# ECDL_CUR_CTRL.net
KiCad netlist of a schematic drawn in EAGLE
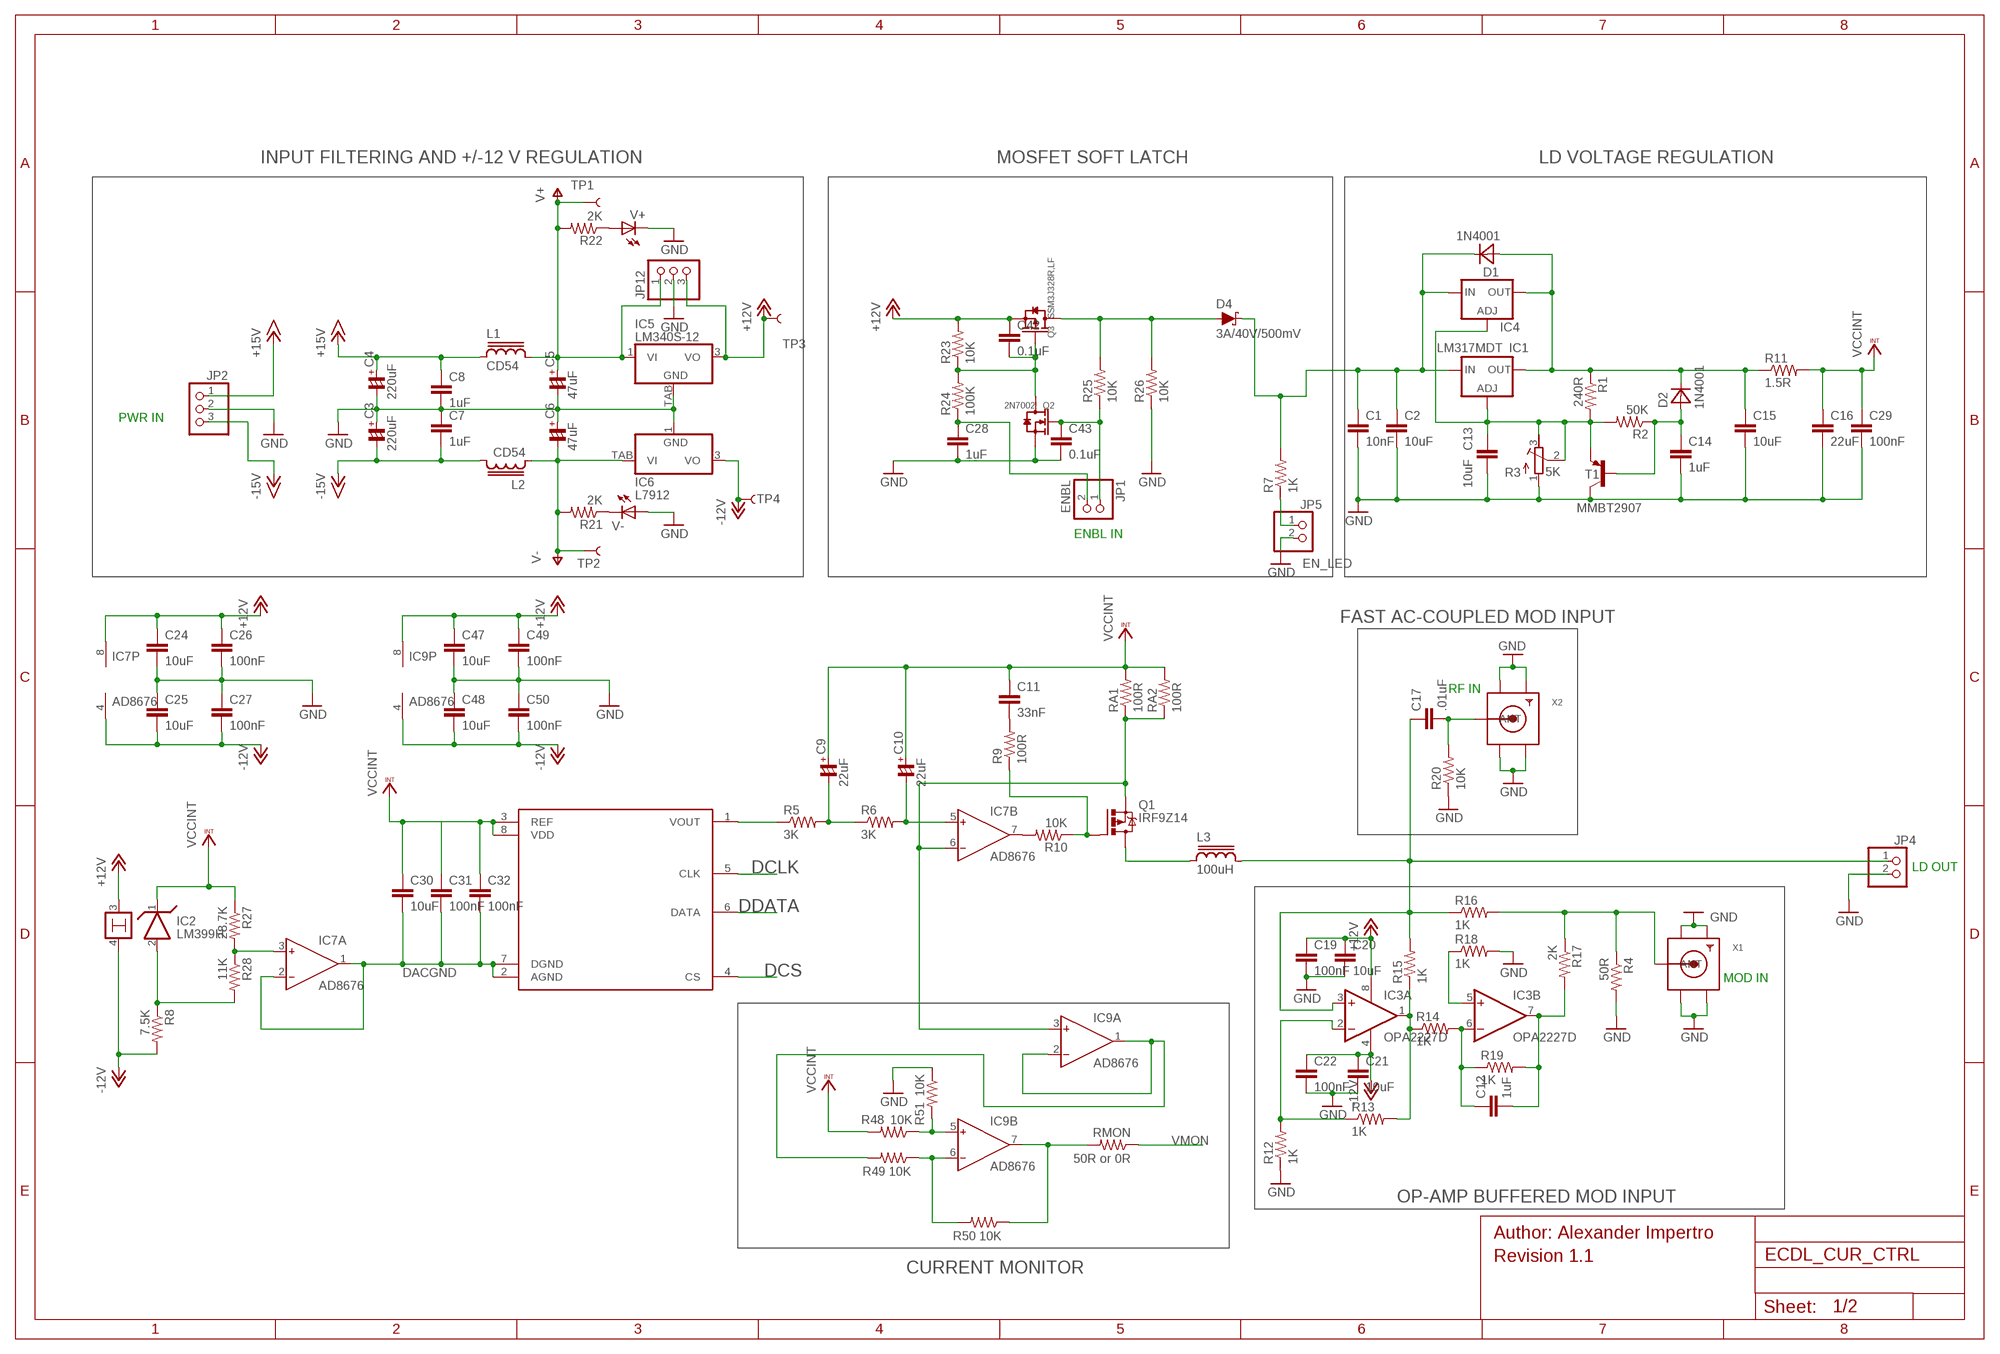
[diagram p0: schematic, sheet 1]
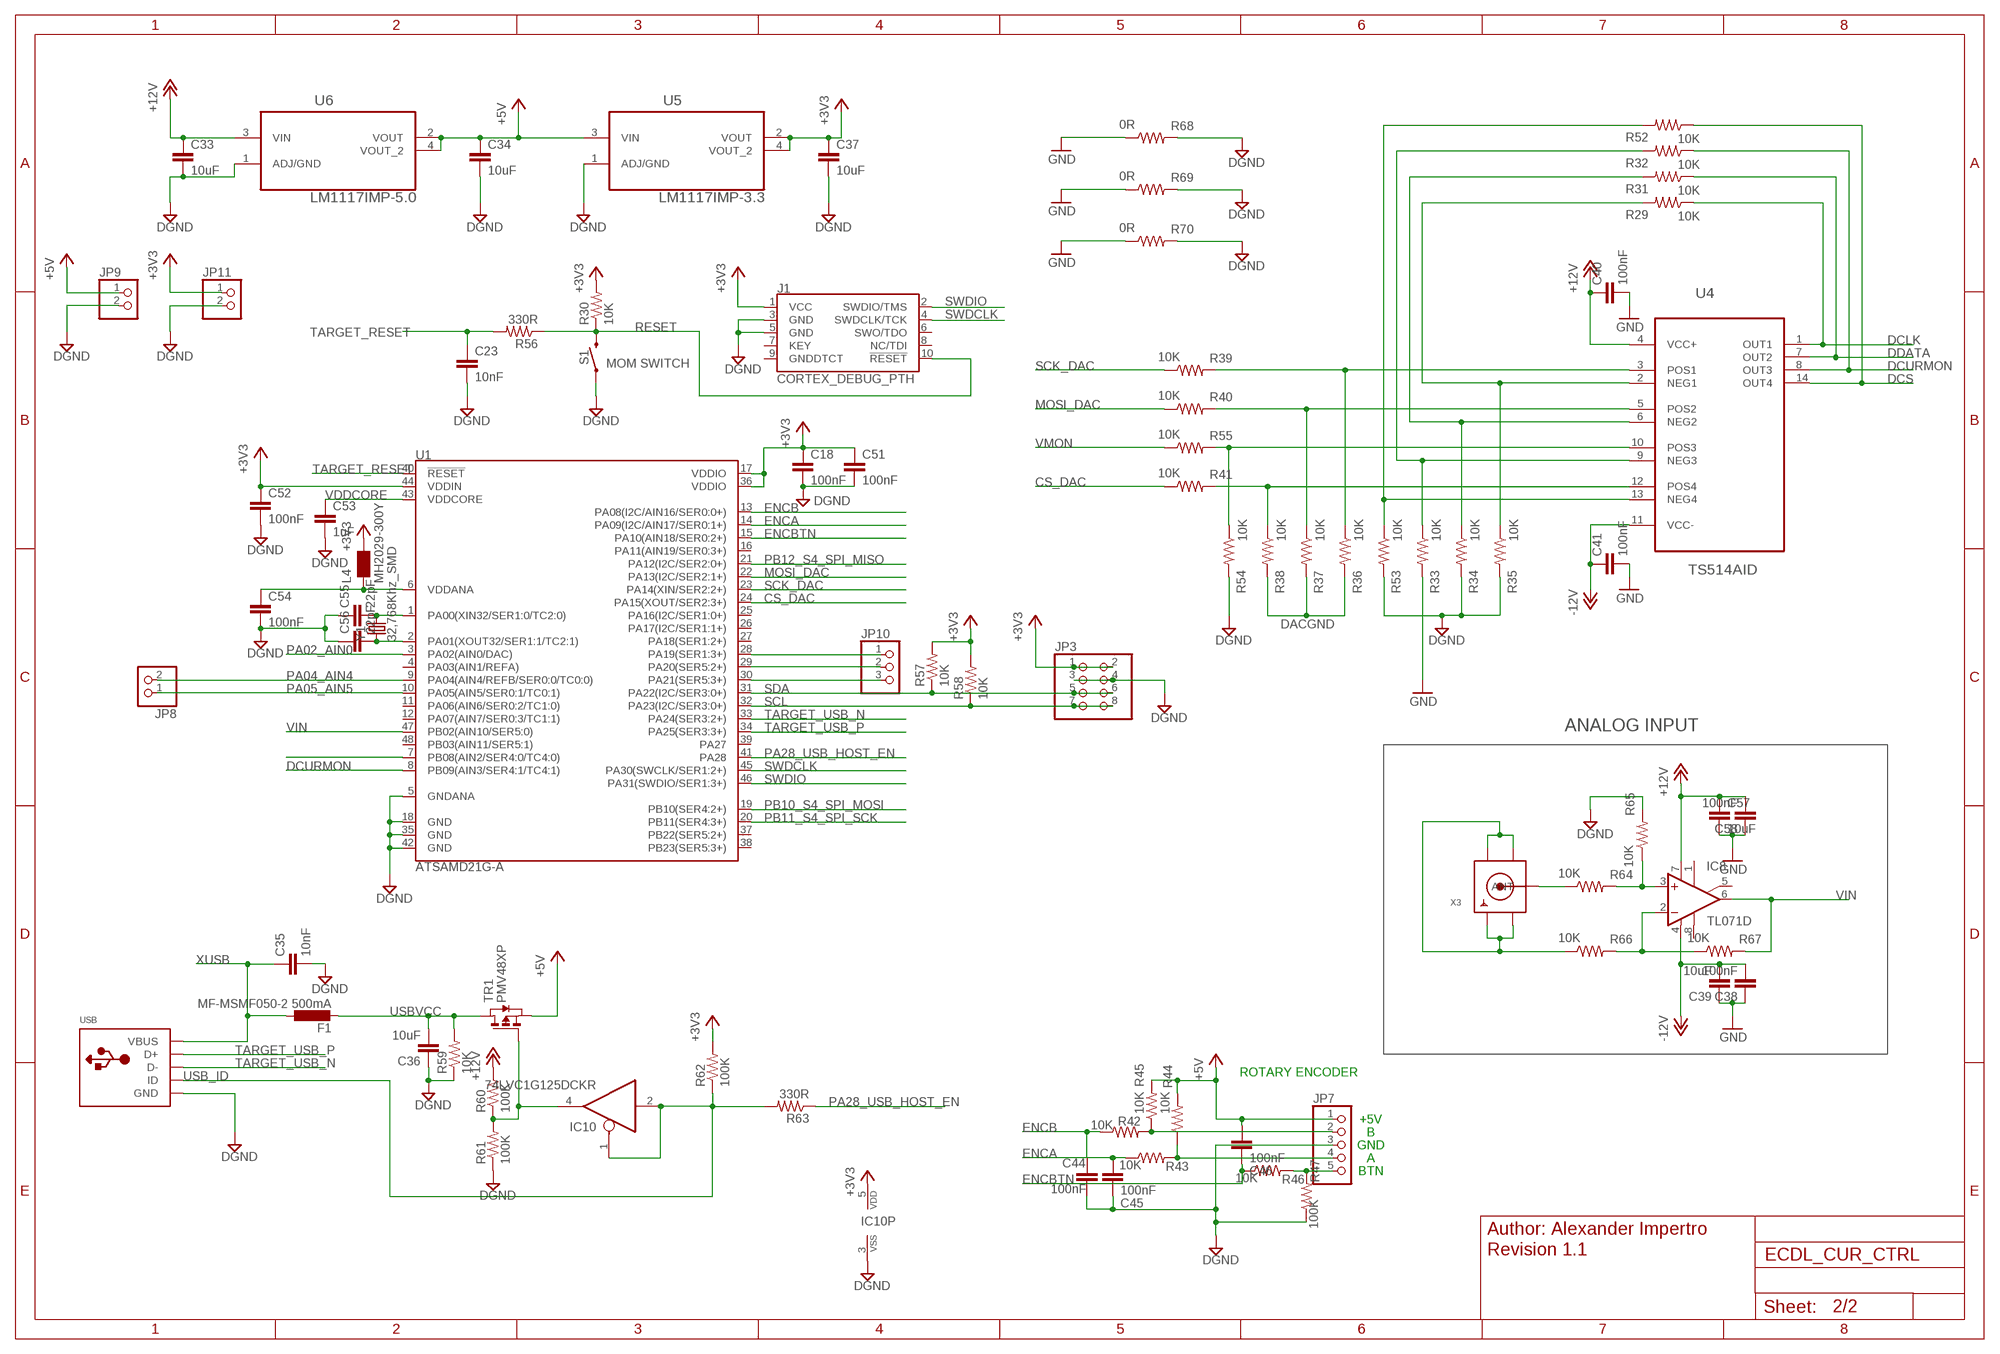
[diagram p1: schematic, sheet 2]

(export (version "E")
  (design (tool "Eeschema 10.0.6"))
  (components
    (comp (ref "C1")
      (value "10nF")
      (footprint "eagle-import:C0805")
      (libsource (lib "eagle-import") (part "C-EUC0805"))
    )
    (comp (ref "C2")
      (value "10uF")
      (footprint "eagle-import:C0805")
      (libsource (lib "eagle-import") (part "C-EUC0805"))
    )
    (comp (ref "C3")
      (value "220uF")
      (footprint "eagle-import:CSV-D")
      (libsource (lib "eagle-import") (part "rc-master-smd_CP_SV-D"))
    )
    (comp (ref "C4")
      (value "220uF")
      (footprint "eagle-import:CSV-D")
      (libsource (lib "eagle-import") (part "rc-master-smd_CP_SV-D"))
    )
    (comp (ref "C5")
      (value "47uF")
      (footprint "eagle-import:C3528-21R_T")
      (libsource (lib "eagle-import") (part "CP_3528-21R"))
    )
    (comp (ref "C6")
      (value "47uF")
      (footprint "eagle-import:C3528-21R_T")
      (libsource (lib "eagle-import") (part "CP_3528-21R"))
    )
    (comp (ref "C7")
      (value "1uF")
      (footprint "eagle-import:C0805")
      (libsource (lib "eagle-import") (part "C-EUC0805"))
    )
    (comp (ref "C8")
      (value "1uF")
      (footprint "eagle-import:C0805")
      (libsource (lib "eagle-import") (part "C-EUC0805"))
    )
    (comp (ref "C9")
      (value "22uF")
      (footprint "eagle-import:CSV-C")
      (libsource (lib "eagle-import") (part "rc-master-smd_CP_SV-C"))
    )
    (comp (ref "C10")
      (value "22uF")
      (footprint "eagle-import:CSV-C")
      (libsource (lib "eagle-import") (part "rc-master-smd_CP_SV-C"))
    )
    (comp (ref "C11")
      (value "33nF")
      (footprint "eagle-import:C0805")
      (libsource (lib "eagle-import") (part "C-EUC0805"))
    )
    (comp (ref "C12")
      (value "1uF")
      (footprint "eagle-import:C0805")
      (libsource (lib "eagle-import") (part "C-EUC0805"))
    )
    (comp (ref "C13")
      (value "10uF")
      (footprint "eagle-import:C0805")
      (libsource (lib "eagle-import") (part "C-EUC0805"))
    )
    (comp (ref "C14")
      (value "1uF")
      (footprint "eagle-import:C0805")
      (libsource (lib "eagle-import") (part "C-EUC0805"))
    )
    (comp (ref "C15")
      (value "10uF")
      (footprint "eagle-import:C0805")
      (libsource (lib "eagle-import") (part "C-EUC0805"))
    )
    (comp (ref "C16")
      (value "22uF")
      (footprint "eagle-import:C0805")
      (libsource (lib "eagle-import") (part "C-EUC0805"))
    )
    (comp (ref "C17")
      (value ".01uF")
      (footprint "eagle-import:C0805")
      (libsource (lib "eagle-import") (part "C-EUC0805"))
    )
    (comp (ref "C19")
      (value "100nF")
      (footprint "eagle-import:C0805")
      (libsource (lib "eagle-import") (part "C-EUC0805"))
    )
    (comp (ref "C20")
      (value "10uF")
      (footprint "eagle-import:C0805")
      (libsource (lib "eagle-import") (part "C-EUC0805"))
    )
    (comp (ref "C21")
      (value "10uF")
      (footprint "eagle-import:C0805")
      (libsource (lib "eagle-import") (part "C-EUC0805"))
    )
    (comp (ref "C22")
      (value "100nF")
      (footprint "eagle-import:C0805")
      (libsource (lib "eagle-import") (part "C-EUC0805"))
    )
    (comp (ref "C24")
      (value "10uF")
      (footprint "eagle-import:C0805")
      (libsource (lib "eagle-import") (part "C-EUC0805"))
    )
    (comp (ref "C25")
      (value "10uF")
      (footprint "eagle-import:C0805")
      (libsource (lib "eagle-import") (part "C-EUC0805"))
    )
    (comp (ref "C26")
      (value "100nF")
      (footprint "eagle-import:C0805")
      (libsource (lib "eagle-import") (part "C-EUC0805"))
    )
    (comp (ref "C27")
      (value "100nF")
      (footprint "eagle-import:C0805")
      (libsource (lib "eagle-import") (part "C-EUC0805"))
    )
    (comp (ref "C28")
      (value "1uF")
      (footprint "eagle-import:C0805")
      (libsource (lib "eagle-import") (part "C-EUC0805"))
    )
    (comp (ref "C29")
      (value "100nF")
      (footprint "eagle-import:C0805")
      (libsource (lib "eagle-import") (part "C-EUC0805"))
    )
    (comp (ref "C30")
      (value "10uF")
      (footprint "eagle-import:C0805")
      (libsource (lib "eagle-import") (part "C-EUC0805"))
    )
    (comp (ref "C31")
      (value "100nF")
      (footprint "eagle-import:C0805")
      (libsource (lib "eagle-import") (part "C-EUC0805"))
    )
    (comp (ref "C32")
      (value "100nF")
      (footprint "eagle-import:C0805")
      (libsource (lib "eagle-import") (part "C-EUC0805"))
    )
    (comp (ref "C42")
      (value "0.1uF")
      (footprint "eagle-import:C0805")
      (libsource (lib "eagle-import") (part "C-EUC0805"))
    )
    (comp (ref "C43")
      (value "0.1uF")
      (footprint "eagle-import:C0805")
      (libsource (lib "eagle-import") (part "C-EUC0805"))
    )
    (comp (ref "C47")
      (value "10uF")
      (footprint "eagle-import:C0805")
      (libsource (lib "eagle-import") (part "C-EUC0805"))
    )
    (comp (ref "C48")
      (value "10uF")
      (footprint "eagle-import:C0805")
      (libsource (lib "eagle-import") (part "C-EUC0805"))
    )
    (comp (ref "C49")
      (value "100nF")
      (footprint "eagle-import:C0805")
      (libsource (lib "eagle-import") (part "C-EUC0805"))
    )
    (comp (ref "C50")
      (value "100nF")
      (footprint "eagle-import:C0805")
      (libsource (lib "eagle-import") (part "C-EUC0805"))
    )
    (comp (ref "D1")
      (value "1N4001")
      (footprint "eagle-import:SMA")
      (libsource (lib "eagle-import") (part "MBRA340T3"))
    )
    (comp (ref "D2")
      (value "1N4001")
      (footprint "eagle-import:SMA")
      (libsource (lib "eagle-import") (part "MBRA340T3"))
    )
    (comp (ref "D4")
      (value "3A/40V/500mV")
      (footprint "eagle-import:SMA-DIODE")
      (libsource (lib "eagle-import") (part "DIODE-SCHOTTKY-B340A"))
    )
    (comp (ref "IC1")
      (value "LM317MDT")
      (footprint "eagle-import:DPACK")
      (libsource (lib "eagle-import") (part "LM317?MDT"))
    )
    (comp (ref "IC2")
      (value "LM399H")
      (footprint "eagle-import:TO39_4")
      (libsource (lib "eagle-import") (part "LM399H"))
    )
    (comp (ref "IC3")
      (value "OPA2227D")
      (footprint "eagle-import:SO08")
      (libsource (lib "eagle-import") (part "OPA222D7"))
    )
    (comp (ref "IC4")
      (value "LM317TS")
      (footprint "eagle-import:317TS")
      (libsource (lib "eagle-import") (part "LM317TS"))
    )
    (comp (ref "IC5")
      (value "LM340S-12")
      (footprint "eagle-import:TO263-3")
      (libsource (lib "eagle-import") (part "LM340?-S12"))
    )
    (comp (ref "IC6")
      (value "L7912")
      (footprint "eagle-import:TO223-3")
      (libsource (lib "eagle-import") (part "L7912"))
    )
    (comp (ref "IC7")
      (value "AD8676")
      (footprint "eagle-import:SO8")
      (fields (field (name "MPN") "AD8656ARZ"))
      (libsource (lib "eagle-import") (part "AD8656R"))
    )
    (comp (ref "IC9")
      (value "AD8676")
      (footprint "eagle-import:SO8")
      (fields (field (name "MPN") "AD8656ARZ"))
      (libsource (lib "eagle-import") (part "AD8656R"))
    )
    (comp (ref "JP1")
      (value "ENBL")
      (footprint "eagle-import:1X02")
      (libsource (lib "eagle-import") (part "PINHD-1X2"))
    )
    (comp (ref "JP2")
      (value "PINHD-1X3/90")
      (footprint "eagle-import:1X03_90")
      (libsource (lib "eagle-import") (part "PINHD-1X3/90"))
    )
    (comp (ref "JP4")
      (value "PINHD-1X2/90")
      (footprint "eagle-import:1X02_90")
      (libsource (lib "eagle-import") (part "PINHD-1X2/90"))
    )
    (comp (ref "JP5")
      (value "EN_LED")
      (footprint "eagle-import:1X02")
      (libsource (lib "eagle-import") (part "PINHD-1X2"))
    )
    (comp (ref "JP12")
      (value "PINHD-1X3")
      (footprint "eagle-import:1X03")
      (libsource (lib "eagle-import") (part "PINHD-1X3"))
    )
    (comp (ref "L1")
      (value "CD54")
      (footprint "eagle-import:CD54")
      (libsource (lib "eagle-import") (part "CD54"))
    )
    (comp (ref "L2")
      (value "CD54")
      (footprint "eagle-import:CD54")
      (libsource (lib "eagle-import") (part "CD54"))
    )
    (comp (ref "L3")
      (value "100uH")
      (footprint "eagle-import:CD54")
      (libsource (lib "eagle-import") (part "CD54"))
    )
    (comp (ref "Q1")
      (value "IRF9Z14")
      (footprint "eagle-import:TO220BV")
      (libsource (lib "eagle-import") (part "IRF9530"))
    )
    (comp (ref "Q2")
      (value "2N7002")
      (footprint "eagle-import:SOT-23")
      (fields (field (name "MPN") "2N7002,215"))
      (libsource (lib "eagle-import") (part "SMD-MOSFET-N-CH-60V-300MA-LOGIC-LEVEL-FET-2N7002(SOT-23)"))
    )
    (comp (ref "Q3")
      (value "SSM3J328R,LF")
      (footprint "eagle-import:SOT-23")
      (libsource (lib "eagle-import") (part "SMD-MOSFET-P-CH-20V-6A-SSM3J328R(SOT-23)"))
    )
    (comp (ref "R1")
      (value "240R")
      (footprint "eagle-import:R0805")
      (libsource (lib "eagle-import") (part "rcl_334_R-US_R0805"))
    )
    (comp (ref "R2")
      (value "50K")
      (footprint "eagle-import:R0805")
      (libsource (lib "eagle-import") (part "rcl_334_R-US_R0805"))
    )
    (comp (ref "R3")
      (value "5K")
      (footprint "eagle-import:RTRIM3296W")
      (libsource (lib "eagle-import") (part "R-TRIMM3296W"))
    )
    (comp (ref "R4")
      (value "50R")
      (footprint "eagle-import:R0805")
      (libsource (lib "eagle-import") (part "rcl_334_R-US_R0805"))
    )
    (comp (ref "R5")
      (value "3K")
      (footprint "eagle-import:R0805")
      (libsource (lib "eagle-import") (part "rcl_334_R-US_R0805"))
    )
    (comp (ref "R6")
      (value "3K")
      (footprint "eagle-import:R0805")
      (libsource (lib "eagle-import") (part "rcl_334_R-US_R0805"))
    )
    (comp (ref "R7")
      (value "1K")
      (footprint "eagle-import:R0805")
      (libsource (lib "eagle-import") (part "rcl_334_R-US_R0805"))
    )
    (comp (ref "R8")
      (value "7.5K")
      (footprint "eagle-import:R0805")
      (libsource (lib "eagle-import") (part "rcl_334_R-US_R0805"))
    )
    (comp (ref "R9")
      (value "100R")
      (footprint "eagle-import:R0805")
      (libsource (lib "eagle-import") (part "rcl_334_R-US_R0805"))
    )
    (comp (ref "R10")
      (value "10K")
      (footprint "eagle-import:R0805")
      (libsource (lib "eagle-import") (part "rcl_334_R-US_R0805"))
    )
    (comp (ref "R11")
      (value "1.5R")
      (footprint "eagle-import:R2512")
      (libsource (lib "eagle-import") (part "R-US_R2512"))
    )
    (comp (ref "R12")
      (value "1K")
      (footprint "eagle-import:R0805")
      (libsource (lib "eagle-import") (part "rcl_334_R-US_R0805"))
    )
    (comp (ref "R13")
      (value "1K")
      (footprint "eagle-import:R0805")
      (libsource (lib "eagle-import") (part "rcl_334_R-US_R0805"))
    )
    (comp (ref "R14")
      (value "1K")
      (footprint "eagle-import:R0805")
      (libsource (lib "eagle-import") (part "rcl_334_R-US_R0805"))
    )
    (comp (ref "R15")
      (value "1K")
      (footprint "eagle-import:R0805")
      (libsource (lib "eagle-import") (part "rcl_334_R-US_R0805"))
    )
    (comp (ref "R16")
      (value "1K")
      (footprint "eagle-import:R0805")
      (libsource (lib "eagle-import") (part "rcl_334_R-US_R0805"))
    )
    (comp (ref "R17")
      (value "2K")
      (footprint "eagle-import:R0805")
      (libsource (lib "eagle-import") (part "rcl_334_R-US_R0805"))
    )
    (comp (ref "R18")
      (value "1K")
      (footprint "eagle-import:R0805")
      (libsource (lib "eagle-import") (part "rcl_334_R-US_R0805"))
    )
    (comp (ref "R19")
      (value "1K")
      (footprint "eagle-import:R0805")
      (libsource (lib "eagle-import") (part "rcl_334_R-US_R0805"))
    )
    (comp (ref "R20")
      (value "10K")
      (footprint "eagle-import:R0805")
      (libsource (lib "eagle-import") (part "rcl_334_R-US_R0805"))
    )
    (comp (ref "R21")
      (value "2K")
      (footprint "eagle-import:R0805")
      (libsource (lib "eagle-import") (part "rcl_334_R-US_R0805"))
    )
    (comp (ref "R22")
      (value "2K")
      (footprint "eagle-import:R0805")
      (libsource (lib "eagle-import") (part "rcl_334_R-US_R0805"))
    )
    (comp (ref "R23")
      (value "10K")
      (footprint "eagle-import:R0805")
      (libsource (lib "eagle-import") (part "rcl_334_R-US_R0805"))
    )
    (comp (ref "R24")
      (value "100K")
      (footprint "eagle-import:R0805")
      (libsource (lib "eagle-import") (part "rcl_334_R-US_R0805"))
    )
    (comp (ref "R25")
      (value "10K")
      (footprint "eagle-import:R0805")
      (libsource (lib "eagle-import") (part "rcl_334_R-US_R0805"))
    )
    (comp (ref "R26")
      (value "10K")
      (footprint "eagle-import:R0805")
      (libsource (lib "eagle-import") (part "rcl_334_R-US_R0805"))
    )
    (comp (ref "R27")
      (value "28.7K")
      (footprint "eagle-import:R0805")
      (libsource (lib "eagle-import") (part "rcl_334_R-US_R0805"))
    )
    (comp (ref "R28")
      (value "11K")
      (footprint "eagle-import:R0805")
      (libsource (lib "eagle-import") (part "rcl_334_R-US_R0805"))
    )
    (comp (ref "R48")
      (value "10K")
      (footprint "eagle-import:R0805")
      (libsource (lib "eagle-import") (part "rcl_334_R-US_R0805"))
    )
    (comp (ref "R49")
      (value "10K")
      (footprint "eagle-import:R0805")
      (libsource (lib "eagle-import") (part "rcl_334_R-US_R0805"))
    )
    (comp (ref "R50")
      (value "10K")
      (footprint "eagle-import:R0805")
      (libsource (lib "eagle-import") (part "rcl_334_R-US_R0805"))
    )
    (comp (ref "R51")
      (value "10K")
      (footprint "eagle-import:R0805")
      (libsource (lib "eagle-import") (part "rcl_334_R-US_R0805"))
    )
    (comp (ref "RA1")
      (value "100R")
      (footprint "eagle-import:R2512")
      (libsource (lib "eagle-import") (part "R-US_R2512"))
    )
    (comp (ref "RA2")
      (value "100R")
      (footprint "eagle-import:R2512")
      (libsource (lib "eagle-import") (part "R-US_R2512"))
    )
    (comp (ref "RMON")
      (value "50R or 0R")
      (footprint "eagle-import:R0805")
      (libsource (lib "eagle-import") (part "rcl_334_R-US_R0805"))
    )
    (comp (ref "T1")
      (value "MMBT2907")
      (footprint "eagle-import:SOT23-BEC")
      (libsource (lib "eagle-import") (part "-PNP-SOT23-BECMMBT2907ALT1"))
    )
    (comp (ref "TP1")
      (value "TEST-POINT2")
      (footprint "eagle-import:PAD.02X.02")
      (libsource (lib "eagle-import") (part "TEST-POINT2"))
    )
    (comp (ref "TP2")
      (value "TEST-POINT2")
      (footprint "eagle-import:PAD.02X.02")
      (libsource (lib "eagle-import") (part "TEST-POINT2"))
    )
    (comp (ref "TP3")
      (value "TEST-POINT2")
      (footprint "eagle-import:PAD.02X.02")
      (libsource (lib "eagle-import") (part "TEST-POINT2"))
    )
    (comp (ref "TP4")
      (value "TEST-POINT2")
      (footprint "eagle-import:PAD.02X.02")
      (libsource (lib "eagle-import") (part "TEST-POINT2"))
    )
    (comp (ref "U3")
      (value "AD5541")
      (footprint "eagle-import:SOIC-8")
      (libsource (lib "eagle-import") (part "AD5541"))
    )
    (comp (ref "V+")
      (value "LEDCHIPLED_0805")
      (footprint "eagle-import:CHIPLED_0805")
      (libsource (lib "eagle-import") (part "LEDCHIPLED_0805"))
    )
    (comp (ref "V-")
      (value "LEDCHIPLED_0805")
      (footprint "eagle-import:CHIPLED_0805")
      (libsource (lib "eagle-import") (part "LEDCHIPLED_0805"))
    )
    (comp (ref "X1")
      (value "SMACONNECTOR")
      (footprint "eagle-import:SMA90_DIP")
      (libsource (lib "eagle-import") (part "SMACONNECTOR"))
    )
    (comp (ref "X2")
      (value "SMACONNECTOR")
      (footprint "eagle-import:SMA90_DIP")
      (libsource (lib "eagle-import") (part "SMACONNECTOR"))
    )
    (comp (ref "C18")
      (value "100nF")
      (footprint "eagle-import:C0805")
      (libsource (lib "eagle-import") (part "C-EUC0805"))
    )
    (comp (ref "C23")
      (value "10nF")
      (footprint "eagle-import:C0805")
      (libsource (lib "eagle-import") (part "C-EUC0805"))
    )
    (comp (ref "C33")
      (value "10uF")
      (footprint "eagle-import:C0805")
      (libsource (lib "eagle-import") (part "C-EUC0805"))
    )
    (comp (ref "C34")
      (value "10uF")
      (footprint "eagle-import:C0805")
      (libsource (lib "eagle-import") (part "C-EUC0805"))
    )
    (comp (ref "C35")
      (value "10nF")
      (footprint "eagle-import:C0805")
      (libsource (lib "eagle-import") (part "C-EUC0805"))
    )
    (comp (ref "C36")
      (value "10uF")
      (footprint "eagle-import:C0805")
      (libsource (lib "eagle-import") (part "C-EUC0805"))
    )
    (comp (ref "C37")
      (value "10uF")
      (footprint "eagle-import:C0805")
      (libsource (lib "eagle-import") (part "C-EUC0805"))
    )
    (comp (ref "C38")
      (value "100nF")
      (footprint "eagle-import:C0805")
      (libsource (lib "eagle-import") (part "C-EUC0805"))
    )
    (comp (ref "C39")
      (value "10uF")
      (footprint "eagle-import:C0805")
      (libsource (lib "eagle-import") (part "C-EUC0805"))
    )
    (comp (ref "C40")
      (value "100nF")
      (footprint "eagle-import:C0805")
      (libsource (lib "eagle-import") (part "C-EUC0805"))
    )
    (comp (ref "C41")
      (value "100nF")
      (footprint "eagle-import:C0805")
      (libsource (lib "eagle-import") (part "C-EUC0805"))
    )
    (comp (ref "C44")
      (value "100nF")
      (footprint "eagle-import:C0805")
      (libsource (lib "eagle-import") (part "C-EUC0805"))
    )
    (comp (ref "C45")
      (value "100nF")
      (footprint "eagle-import:C0805")
      (libsource (lib "eagle-import") (part "C-EUC0805"))
    )
    (comp (ref "C46")
      (value "100nF")
      (footprint "eagle-import:C0805")
      (libsource (lib "eagle-import") (part "C-EUC0805"))
    )
    (comp (ref "C51")
      (value "100nF")
      (footprint "eagle-import:C0805")
      (libsource (lib "eagle-import") (part "C-EUC0805"))
    )
    (comp (ref "C52")
      (value "100nF")
      (footprint "eagle-import:C0805")
      (libsource (lib "eagle-import") (part "C-EUC0805"))
    )
    (comp (ref "C53")
      (value "1uF")
      (footprint "eagle-import:C0805")
      (libsource (lib "eagle-import") (part "C-EUC0805"))
    )
    (comp (ref "C54")
      (value "100nF")
      (footprint "eagle-import:C0805")
      (libsource (lib "eagle-import") (part "C-EUC0805"))
    )
    (comp (ref "C55")
      (value "22pF")
      (footprint "eagle-import:C0805")
      (libsource (lib "eagle-import") (part "C-EUC0805"))
    )
    (comp (ref "C56")
      (value "22pF")
      (footprint "eagle-import:C0805")
      (libsource (lib "eagle-import") (part "C-EUC0805"))
    )
    (comp (ref "C57")
      (value "10uF")
      (footprint "eagle-import:C0805")
      (libsource (lib "eagle-import") (part "C-EUC0805"))
    )
    (comp (ref "C58")
      (value "100nF")
      (footprint "eagle-import:C0805")
      (libsource (lib "eagle-import") (part "C-EUC0805"))
    )
    (comp (ref "F1")
      (value "MF-MSMF050-2 500mA")
      (footprint "eagle-import:PROTEZIONE_L1812")
      (fields (field (name "PART_NUMBER") "MF-MSMF050-2"))
      (libsource (lib "eagle-import") (part "PROTEZIONE_0002_MF-MSMF050-2"))
    )
    (comp (ref "IC8")
      (value "TL071D")
      (footprint "eagle-import:SO08")
      (libsource (lib "eagle-import") (part "TL071D"))
    )
    (comp (ref "IC10")
      (value "74LVC1G125DCKR")
      (footprint "eagle-import:INTEGRATEDCIRCUITS_SC70-5")
      (fields (field (name "PART_NUMBER") "SN74LVC1G125DCKR"))
      (libsource (lib "eagle-import") (part "INTEGRATEDCIRCUITS_0040_SN74LVC1G125DCKR"))
    )
    (comp (ref "J1")
      (value "CORTEX_DEBUG_PTH")
      (footprint "eagle-import:2X5-PTH-1.27MM")
      (libsource (lib "eagle-import") (part "CORTEX_DEBUG_PTH"))
    )
    (comp (ref "JP3")
      (value "PINHD-2X4")
      (footprint "eagle-import:2X04")
      (libsource (lib "eagle-import") (part "PINHD-2X4"))
    )
    (comp (ref "JP7")
      (value "PINHD-1X5")
      (footprint "eagle-import:1X05")
      (libsource (lib "eagle-import") (part "PINHD-1X5"))
    )
    (comp (ref "JP8")
      (value "PINHD-1X2")
      (footprint "eagle-import:1X02")
      (libsource (lib "eagle-import") (part "PINHD-1X2"))
    )
    (comp (ref "JP9")
      (value "PINHD-1X2")
      (footprint "eagle-import:1X02")
      (libsource (lib "eagle-import") (part "PINHD-1X2"))
    )
    (comp (ref "JP10")
      (value "PINHD-1X3")
      (footprint "eagle-import:1X03")
      (libsource (lib "eagle-import") (part "PINHD-1X3"))
    )
    (comp (ref "JP11")
      (value "PINHD-1X2")
      (footprint "eagle-import:1X02")
      (libsource (lib "eagle-import") (part "PINHD-1X2"))
    )
    (comp (ref "L4")
      (value "MH2029-300Y")
      (footprint "eagle-import:PROTEZIONE_0805")
      (fields (field (name "PART_NUMBER") "BLM21PG300SN1D_/_MH2029-300Y"))
      (libsource (lib "eagle-import") (part "PROTEZIONE_0001_BLM21PG300SN1D_/_MH2029-300Y"))
    )
    (comp (ref "R29")
      (value "10K")
      (footprint "eagle-import:R0805")
      (libsource (lib "eagle-import") (part "rcl_334_R-US_R0805"))
    )
    (comp (ref "R30")
      (value "10K")
      (footprint "eagle-import:R0805")
      (libsource (lib "eagle-import") (part "rcl_334_R-US_R0805"))
    )
    (comp (ref "R31")
      (value "10K")
      (footprint "eagle-import:R0805")
      (libsource (lib "eagle-import") (part "rcl_334_R-US_R0805"))
    )
    (comp (ref "R32")
      (value "10K")
      (footprint "eagle-import:R0805")
      (libsource (lib "eagle-import") (part "rcl_334_R-US_R0805"))
    )
    (comp (ref "R33")
      (value "10K")
      (footprint "eagle-import:R0805")
      (libsource (lib "eagle-import") (part "rcl_334_R-US_R0805"))
    )
    (comp (ref "R34")
      (value "10K")
      (footprint "eagle-import:R0805")
      (libsource (lib "eagle-import") (part "rcl_334_R-US_R0805"))
    )
    (comp (ref "R35")
      (value "10K")
      (footprint "eagle-import:R0805")
      (libsource (lib "eagle-import") (part "rcl_334_R-US_R0805"))
    )
    (comp (ref "R36")
      (value "10K")
      (footprint "eagle-import:R0805")
      (libsource (lib "eagle-import") (part "rcl_334_R-US_R0805"))
    )
    (comp (ref "R37")
      (value "10K")
      (footprint "eagle-import:R0805")
      (libsource (lib "eagle-import") (part "rcl_334_R-US_R0805"))
    )
    (comp (ref "R38")
      (value "10K")
      (footprint "eagle-import:R0805")
      (libsource (lib "eagle-import") (part "rcl_334_R-US_R0805"))
    )
    (comp (ref "R39")
      (value "10K")
      (footprint "eagle-import:R0805")
      (libsource (lib "eagle-import") (part "rcl_334_R-US_R0805"))
    )
    (comp (ref "R40")
      (value "10K")
      (footprint "eagle-import:R0805")
      (libsource (lib "eagle-import") (part "rcl_334_R-US_R0805"))
    )
    (comp (ref "R41")
      (value "10K")
      (footprint "eagle-import:R0805")
      (libsource (lib "eagle-import") (part "rcl_334_R-US_R0805"))
    )
    (comp (ref "R42")
      (value "10K")
      (footprint "eagle-import:R0805")
      (libsource (lib "eagle-import") (part "rcl_334_R-US_R0805"))
    )
    (comp (ref "R43")
      (value "10K")
      (footprint "eagle-import:R0805")
      (libsource (lib "eagle-import") (part "rcl_334_R-US_R0805"))
    )
    (comp (ref "R44")
      (value "10K")
      (footprint "eagle-import:R0805")
      (libsource (lib "eagle-import") (part "rcl_334_R-US_R0805"))
    )
    (comp (ref "R45")
      (value "10K")
      (footprint "eagle-import:R0805")
      (libsource (lib "eagle-import") (part "rcl_334_R-US_R0805"))
    )
    (comp (ref "R46")
      (value "10K")
      (footprint "eagle-import:R0805")
      (libsource (lib "eagle-import") (part "rcl_334_R-US_R0805"))
    )
    (comp (ref "R47")
      (value "100K")
      (footprint "eagle-import:R0805")
      (libsource (lib "eagle-import") (part "rcl_334_R-US_R0805"))
    )
    (comp (ref "R52")
      (value "10K")
      (footprint "eagle-import:R0805")
      (libsource (lib "eagle-import") (part "rcl_334_R-US_R0805"))
    )
    (comp (ref "R53")
      (value "10K")
      (footprint "eagle-import:R0805")
      (libsource (lib "eagle-import") (part "rcl_334_R-US_R0805"))
    )
    (comp (ref "R54")
      (value "10K")
      (footprint "eagle-import:R0805")
      (libsource (lib "eagle-import") (part "rcl_334_R-US_R0805"))
    )
    (comp (ref "R55")
      (value "10K")
      (footprint "eagle-import:R0805")
      (libsource (lib "eagle-import") (part "rcl_334_R-US_R0805"))
    )
    (comp (ref "R56")
      (value "330R")
      (footprint "eagle-import:R0805")
      (libsource (lib "eagle-import") (part "rcl_334_R-US_R0805"))
    )
    (comp (ref "R57")
      (value "10K")
      (footprint "eagle-import:R0805")
      (libsource (lib "eagle-import") (part "rcl_334_R-US_R0805"))
    )
    (comp (ref "R58")
      (value "10K")
      (footprint "eagle-import:R0805")
      (libsource (lib "eagle-import") (part "rcl_334_R-US_R0805"))
    )
    (comp (ref "R59")
      (value "10K")
      (footprint "eagle-import:R0805")
      (libsource (lib "eagle-import") (part "rcl_334_R-US_R0805"))
    )
    (comp (ref "R60")
      (value "100K")
      (footprint "eagle-import:R0805")
      (libsource (lib "eagle-import") (part "rcl_334_R-US_R0805"))
    )
    (comp (ref "R61")
      (value "100K")
      (footprint "eagle-import:R0805")
      (libsource (lib "eagle-import") (part "rcl_334_R-US_R0805"))
    )
    (comp (ref "R62")
      (value "100K")
      (footprint "eagle-import:R0805")
      (libsource (lib "eagle-import") (part "rcl_334_R-US_R0805"))
    )
    (comp (ref "R63")
      (value "330R")
      (footprint "eagle-import:R0805")
      (libsource (lib "eagle-import") (part "rcl_334_R-US_R0805"))
    )
    (comp (ref "R64")
      (value "10K")
      (footprint "eagle-import:R0805")
      (libsource (lib "eagle-import") (part "rcl_334_R-US_R0805"))
    )
    (comp (ref "R65")
      (value "10K")
      (footprint "eagle-import:R0805")
      (libsource (lib "eagle-import") (part "rcl_334_R-US_R0805"))
    )
    (comp (ref "R66")
      (value "10K")
      (footprint "eagle-import:R0805")
      (libsource (lib "eagle-import") (part "rcl_334_R-US_R0805"))
    )
    (comp (ref "R67")
      (value "10K")
      (footprint "eagle-import:R0805")
      (libsource (lib "eagle-import") (part "rcl_334_R-US_R0805"))
    )
    (comp (ref "R68")
      (value "0R")
      (footprint "eagle-import:R0805")
      (libsource (lib "eagle-import") (part "rcl_334_R-US_R0805"))
    )
    (comp (ref "R69")
      (value "0R")
      (footprint "eagle-import:R0805")
      (libsource (lib "eagle-import") (part "rcl_334_R-US_R0805"))
    )
    (comp (ref "R70")
      (value "0R")
      (footprint "eagle-import:R0805")
      (libsource (lib "eagle-import") (part "rcl_334_R-US_R0805"))
    )
    (comp (ref "S1")
      (value "MOM SWITCH")
      (footprint "eagle-import:TACTILE_SWITCH_SMD_5.2MM")
      (libsource (lib "eagle-import") (part "MOMENTARY-SWITCH-SPST-SMD-5.2MM"))
    )
    (comp (ref "TR1")
      (value "PMV48XP")
      (footprint "eagle-import:TRANSISTORS_SOT-23")
      (libsource (lib "eagle-import") (part "TRANSISTORS_0297_PMV48XP"))
    )
    (comp (ref "U1")
      (value "ATSAMD21G-A")
      (footprint "eagle-import:TQFP-48")
      (libsource (lib "eagle-import") (part "ATSAMD21G-A"))
    )
    (comp (ref "U4")
      (value "TS514AID")
      (footprint "eagle-import:SOIC127P600X175-14N")
      (libsource (lib "eagle-import") (part "TS514AID"))
    )
    (comp (ref "U5")
      (value "LM1117IMP-3.3")
      (footprint "eagle-import:SOT230P696X180-4N")
      (libsource (lib "eagle-import") (part "LM1117IMP-3.3"))
    )
    (comp (ref "U6")
      (value "LM1117IMP-5.0")
      (footprint "eagle-import:SOT230P696X180-4N")
      (libsource (lib "eagle-import") (part "LM1117IMP-5.0"))
    )
    (comp (ref "USB")
      (value "USBMINIB")
      (footprint "eagle-import:USB-MINIB")
      (libsource (lib "eagle-import") (part "USBMINIB"))
    )
    (comp (ref "X3")
      (value "SMACONNECTOR")
      (footprint "eagle-import:SMA90_DIP")
      (libsource (lib "eagle-import") (part "SMACONNECTOR"))
    )
    (comp (ref "Y1")
      (value "32,768Khz_SMD")
      (footprint "eagle-import:CRISTALLI_RESONATOR_EPSON_FC_145")
      (fields (field (name "PART_NUMBER") "ABS07-32.768KHZ-T"))
      (libsource (lib "eagle-import") (part "CRISTALLI_0213_ABS07-32.768KHZ-T"))
    )
  )
  (nets
    (net (code "1") (name "+3V3") (class "Default")
      (node (ref "C18") (pin "1") (pinfunction "1_1") (pintype "passive"))
      (node (ref "C37") (pin "1") (pinfunction "1_1") (pintype "passive"))
      (node (ref "C51") (pin "1") (pinfunction "1_1") (pintype "passive"))
      (node (ref "C52") (pin "1") (pinfunction "1_1") (pintype "passive"))
      (node (ref "IC10") (pin "5") (pinfunction "VDD_5") (pintype "power_in"))
      (node (ref "J1") (pin "1") (pinfunction "VCC_1") (pintype "bidirectional"))
      (node (ref "JP11") (pin "1") (pinfunction "1_1") (pintype "passive"))
      (node (ref "JP3") (pin "1") (pinfunction "1_1") (pintype "passive"))
      (node (ref "JP3") (pin "2") (pinfunction "2_2") (pintype "passive"))
      (node (ref "L4") (pin "2") (pinfunction "2_2") (pintype "passive"))
      (node (ref "R30") (pin "2") (pinfunction "2_2") (pintype "passive"))
      (node (ref "R57") (pin "2") (pinfunction "2_2") (pintype "passive"))
      (node (ref "R58") (pin "2") (pinfunction "2_2") (pintype "passive"))
      (node (ref "R62") (pin "2") (pinfunction "2_2") (pintype "passive"))
      (node (ref "U1") (pin "17") (pinfunction "VDDIO_17") (pintype "bidirectional"))
      (node (ref "U1") (pin "36") (pinfunction "VDDIO_36") (pintype "bidirectional"))
      (node (ref "U1") (pin "44") (pinfunction "VDDIN_44") (pintype "bidirectional"))
      (node (ref "U5") (pin "2") (pinfunction "VOUT_2") (pintype "output"))
      (node (ref "U5") (pin "4") (pinfunction "VOUT_2_4") (pintype "output"))
    )
    (net (code "2") (name "+5V") (class "Default")
      (node (ref "C34") (pin "1") (pinfunction "1_1") (pintype "passive"))
      (node (ref "C46") (pin "1") (pinfunction "1_1") (pintype "passive"))
      (node (ref "JP7") (pin "1") (pinfunction "1_1") (pintype "passive"))
      (node (ref "JP9") (pin "1") (pinfunction "1_1") (pintype "passive"))
      (node (ref "R44") (pin "2") (pinfunction "2_2") (pintype "passive"))
      (node (ref "R45") (pin "2") (pinfunction "2_2") (pintype "passive"))
      (node (ref "TR1") (pin "2") (pinfunction "S_2") (pintype "passive"))
      (node (ref "U5") (pin "3") (pinfunction "VIN_3") (pintype "input"))
      (node (ref "U6") (pin "2") (pinfunction "VOUT_2") (pintype "output"))
      (node (ref "U6") (pin "4") (pinfunction "VOUT_2_4") (pintype "output"))
    )
    (net (code "3") (name "+12V") (class "Default")
      (node (ref "C19") (pin "1") (pinfunction "1_1") (pintype "passive"))
      (node (ref "C20") (pin "1") (pinfunction "1_1") (pintype "passive"))
      (node (ref "C24") (pin "1") (pinfunction "1_1") (pintype "passive"))
      (node (ref "C26") (pin "1") (pinfunction "1_1") (pintype "passive"))
      (node (ref "C33") (pin "1") (pinfunction "1_1") (pintype "passive"))
      (node (ref "C40") (pin "1") (pinfunction "1_1") (pintype "passive"))
      (node (ref "C42") (pin "1") (pinfunction "1_1") (pintype "passive"))
      (node (ref "C47") (pin "1") (pinfunction "1_1") (pintype "passive"))
      (node (ref "C49") (pin "1") (pinfunction "1_1") (pintype "passive"))
      (node (ref "C57") (pin "1") (pinfunction "1_1") (pintype "passive"))
      (node (ref "C58") (pin "2") (pinfunction "2_2") (pintype "passive"))
      (node (ref "IC2") (pin "3") (pinfunction "3_3") (pintype "input"))
      (node (ref "IC3") (pin "8") (pinfunction "V+_8") (pintype "power_in"))
      (node (ref "IC5") (pin "3") (pinfunction "VO_3") (pintype "passive"))
      (node (ref "IC7") (pin "8") (pinfunction "V+_8") (pintype "power_in"))
      (node (ref "IC8") (pin "7") (pinfunction "V+_7") (pintype "power_in"))
      (node (ref "IC9") (pin "8") (pinfunction "V+_8") (pintype "power_in"))
      (node (ref "JP12") (pin "3") (pinfunction "3_3") (pintype "passive"))
      (node (ref "Q3") (pin "2") (pinfunction "S_2") (pintype "passive"))
      (node (ref "R23") (pin "2") (pinfunction "2_2") (pintype "passive"))
      (node (ref "R60") (pin "2") (pinfunction "2_2") (pintype "passive"))
      (node (ref "TP3") (pin "P$1") (pinfunction "1_P$1") (pintype "bidirectional"))
      (node (ref "U4") (pin "4") (pinfunction "VCC+_4") (pintype "power_in"))
      (node (ref "U6") (pin "3") (pinfunction "VIN_3") (pintype "input"))
    )
    (net (code "4") (name "+15V") (class "Default")
      (node (ref "C4") (pin "+") (pinfunction "+_+") (pintype "passive"))
      (node (ref "C8") (pin "1") (pinfunction "1_1") (pintype "passive"))
      (node (ref "JP2") (pin "1") (pinfunction "1_1") (pintype "passive"))
      (node (ref "L1") (pin "1") (pinfunction "1_1") (pintype "passive"))
    )
    (net (code "5") (name "-12V") (class "Default")
      (node (ref "C21") (pin "1") (pinfunction "1_1") (pintype "passive"))
      (node (ref "C22") (pin "1") (pinfunction "1_1") (pintype "passive"))
      (node (ref "C25") (pin "2") (pinfunction "2_2") (pintype "passive"))
      (node (ref "C27") (pin "2") (pinfunction "2_2") (pintype "passive"))
      (node (ref "C38") (pin "2") (pinfunction "2_2") (pintype "passive"))
      (node (ref "C39") (pin "2") (pinfunction "2_2") (pintype "passive"))
      (node (ref "C41") (pin "1") (pinfunction "1_1") (pintype "passive"))
      (node (ref "C48") (pin "2") (pinfunction "2_2") (pintype "passive"))
      (node (ref "C50") (pin "2") (pinfunction "2_2") (pintype "passive"))
      (node (ref "IC2") (pin "4") (pinfunction "4_4") (pintype "input"))
      (node (ref "IC3") (pin "4") (pinfunction "V-_4") (pintype "power_in"))
      (node (ref "IC6") (pin "3") (pinfunction "VO_3") (pintype "passive"))
      (node (ref "IC7") (pin "4") (pinfunction "V-_4") (pintype "power_in"))
      (node (ref "IC8") (pin "4") (pinfunction "V-_4") (pintype "power_in"))
      (node (ref "IC9") (pin "4") (pinfunction "V-_4") (pintype "power_in"))
      (node (ref "R8") (pin "2") (pinfunction "2_2") (pintype "passive"))
      (node (ref "TP4") (pin "P$1") (pinfunction "1_P$1") (pintype "bidirectional"))
      (node (ref "U4") (pin "11") (pinfunction "VCC-_11") (pintype "power_in"))
    )
    (net (code "6") (name "-15V") (class "Default")
      (node (ref "C3") (pin "-") (pinfunction "-_-") (pintype "passive"))
      (node (ref "C7") (pin "2") (pinfunction "2_2") (pintype "passive"))
      (node (ref "JP2") (pin "3") (pinfunction "3_3") (pintype "passive"))
      (node (ref "L2") (pin "2") (pinfunction "2_2") (pintype "passive"))
    )
    (net (code "7") (name "CS_DAC") (class "Default")
      (node (ref "R41") (pin "1") (pinfunction "1_1") (pintype "passive"))
      (node (ref "U1") (pin "24") (pinfunction "PA15(XOUT/SER2:3+)_24") (pintype "bidirectional"))
    )
    (net (code "8") (name "DACGND") (class "Default")
      (node (ref "C30") (pin "2") (pinfunction "2_2") (pintype "passive"))
      (node (ref "C31") (pin "2") (pinfunction "2_2") (pintype "passive"))
      (node (ref "C32") (pin "2") (pinfunction "2_2") (pintype "passive"))
      (node (ref "IC7") (pin "1") (pinfunction "OUT_1") (pintype "output"))
      (node (ref "IC7") (pin "2") (pinfunction "IN-_2") (pintype "input"))
      (node (ref "R36") (pin "2") (pinfunction "2_2") (pintype "passive"))
      (node (ref "R37") (pin "2") (pinfunction "2_2") (pintype "passive"))
      (node (ref "R38") (pin "2") (pinfunction "2_2") (pintype "passive"))
      (node (ref "U3") (pin "2") (pinfunction "AGND_2") (pintype "bidirectional"))
      (node (ref "U3") (pin "7") (pinfunction "DGND_7") (pintype "bidirectional"))
    )
    (net (code "9") (name "DCLK") (class "Default")
      (node (ref "R29") (pin "1") (pinfunction "1_1") (pintype "passive"))
      (node (ref "U3") (pin "5") (pinfunction "CLK_5") (pintype "bidirectional"))
      (node (ref "U4") (pin "1") (pinfunction "OUT1_1") (pintype "output"))
    )
    (net (code "10") (name "DCS") (class "Default")
      (node (ref "R52") (pin "1") (pinfunction "1_1") (pintype "passive"))
      (node (ref "U3") (pin "4") (pinfunction "CS_4") (pintype "bidirectional"))
      (node (ref "U4") (pin "14") (pinfunction "OUT4_14") (pintype "output"))
    )
    (net (code "11") (name "DCURMON") (class "Default")
      (node (ref "R32") (pin "1") (pinfunction "1_1") (pintype "passive"))
      (node (ref "U1") (pin "8") (pinfunction "PB09(AIN3/SER4:1/TC4:1)_8") (pintype "bidirectional"))
      (node (ref "U4") (pin "8") (pinfunction "OUT3_8") (pintype "output"))
    )
    (net (code "12") (name "DDATA") (class "Default")
      (node (ref "R31") (pin "1") (pinfunction "1_1") (pintype "passive"))
      (node (ref "U3") (pin "6") (pinfunction "DATA_6") (pintype "bidirectional"))
      (node (ref "U4") (pin "7") (pinfunction "OUT2_7") (pintype "output"))
    )
    (net (code "13") (name "DGND") (class "Default")
      (node (ref "C18") (pin "2") (pinfunction "2_2") (pintype "passive"))
      (node (ref "C23") (pin "2") (pinfunction "2_2") (pintype "passive"))
      (node (ref "C33") (pin "2") (pinfunction "2_2") (pintype "passive"))
      (node (ref "C34") (pin "2") (pinfunction "2_2") (pintype "passive"))
      (node (ref "C35") (pin "2") (pinfunction "2_2") (pintype "passive"))
      (node (ref "C36") (pin "1") (pinfunction "1_1") (pintype "passive"))
      (node (ref "C37") (pin "2") (pinfunction "2_2") (pintype "passive"))
      (node (ref "C44") (pin "2") (pinfunction "2_2") (pintype "passive"))
      (node (ref "C45") (pin "2") (pinfunction "2_2") (pintype "passive"))
      (node (ref "C51") (pin "2") (pinfunction "2_2") (pintype "passive"))
      (node (ref "C52") (pin "2") (pinfunction "2_2") (pintype "passive"))
      (node (ref "C53") (pin "2") (pinfunction "2_2") (pintype "passive"))
      (node (ref "C54") (pin "2") (pinfunction "2_2") (pintype "passive"))
      (node (ref "C55") (pin "1") (pinfunction "1_1") (pintype "passive"))
      (node (ref "C56") (pin "1") (pinfunction "1_1") (pintype "passive"))
      (node (ref "IC10") (pin "3") (pinfunction "VSS_3") (pintype "power_in"))
      (node (ref "J1") (pin "3") (pinfunction "GND_3") (pintype "bidirectional"))
      (node (ref "J1") (pin "5") (pinfunction "GND_5") (pintype "bidirectional"))
      (node (ref "JP11") (pin "2") (pinfunction "2_2") (pintype "passive"))
      (node (ref "JP3") (pin "3") (pinfunction "3_3") (pintype "passive"))
      (node (ref "JP3") (pin "4") (pinfunction "4_4") (pintype "passive"))
      (node (ref "JP7") (pin "3") (pinfunction "3_3") (pintype "passive"))
      (node (ref "JP9") (pin "2") (pinfunction "2_2") (pintype "passive"))
      (node (ref "R34") (pin "2") (pinfunction "2_2") (pintype "passive"))
      (node (ref "R35") (pin "2") (pinfunction "2_2") (pintype "passive"))
      (node (ref "R47") (pin "1") (pinfunction "1_1") (pintype "passive"))
      (node (ref "R53") (pin "2") (pinfunction "2_2") (pintype "passive"))
      (node (ref "R54") (pin "2") (pinfunction "2_2") (pintype "passive"))
      (node (ref "R59") (pin "1") (pinfunction "1_1") (pintype "passive"))
      (node (ref "R61") (pin "1") (pinfunction "1_1") (pintype "passive"))
      (node (ref "R65") (pin "2") (pinfunction "2_2") (pintype "passive"))
      (node (ref "R68") (pin "2") (pinfunction "2_2") (pintype "passive"))
      (node (ref "R69") (pin "2") (pinfunction "2_2") (pintype "passive"))
      (node (ref "R70") (pin "2") (pinfunction "2_2") (pintype "passive"))
      (node (ref "S1") (pin "1") (pinfunction "1_1") (pintype "passive"))
      (node (ref "U1") (pin "18") (pinfunction "GND_18") (pintype "bidirectional"))
      (node (ref "U1") (pin "35") (pinfunction "GND_35") (pintype "bidirectional"))
      (node (ref "U1") (pin "42") (pinfunction "GND_42") (pintype "bidirectional"))
      (node (ref "U1") (pin "5") (pinfunction "GNDANA_5") (pintype "bidirectional"))
      (node (ref "U5") (pin "1") (pinfunction "ADJ/GND_1") (pintype "passive"))
      (node (ref "U6") (pin "1") (pinfunction "ADJ/GND_1") (pintype "passive"))
      (node (ref "USB") (pin "GND") (pinfunction "GND_GND") (pintype "power_in"))
    )
    (net (code "14") (name "ENCA") (class "Default")
      (node (ref "C45") (pin "1") (pinfunction "1_1") (pintype "passive"))
      (node (ref "R43") (pin "1") (pinfunction "1_1") (pintype "passive"))
      (node (ref "U1") (pin "14") (pinfunction "PA09(I2C/AIN17/SER0:1+)_14") (pintype "bidirectional"))
    )
    (net (code "15") (name "ENCB") (class "Default")
      (node (ref "C44") (pin "1") (pinfunction "1_1") (pintype "passive"))
      (node (ref "R42") (pin "1") (pinfunction "1_1") (pintype "passive"))
      (node (ref "U1") (pin "13") (pinfunction "PA08(I2C/AIN16/SER0:0+)_13") (pintype "bidirectional"))
    )
    (net (code "16") (name "ENCBTN") (class "Default")
      (node (ref "C46") (pin "2") (pinfunction "2_2") (pintype "passive"))
      (node (ref "R46") (pin "1") (pinfunction "1_1") (pintype "passive"))
      (node (ref "U1") (pin "15") (pinfunction "PA10(AIN18/SER0:2+)_15") (pintype "bidirectional"))
    )
    (net (code "17") (name "GND") (class "Default")
      (node (ref "C1") (pin "2") (pinfunction "2_2") (pintype "passive"))
      (node (ref "C13") (pin "2") (pinfunction "2_2") (pintype "passive"))
      (node (ref "C14") (pin "2") (pinfunction "2_2") (pintype "passive"))
      (node (ref "C15") (pin "2") (pinfunction "2_2") (pintype "passive"))
      (node (ref "C16") (pin "2") (pinfunction "2_2") (pintype "passive"))
      (node (ref "C19") (pin "2") (pinfunction "2_2") (pintype "passive"))
      (node (ref "C2") (pin "2") (pinfunction "2_2") (pintype "passive"))
      (node (ref "C20") (pin "2") (pinfunction "2_2") (pintype "passive"))
      (node (ref "C21") (pin "2") (pinfunction "2_2") (pintype "passive"))
      (node (ref "C22") (pin "2") (pinfunction "2_2") (pintype "passive"))
      (node (ref "C24") (pin "2") (pinfunction "2_2") (pintype "passive"))
      (node (ref "C25") (pin "1") (pinfunction "1_1") (pintype "passive"))
      (node (ref "C26") (pin "2") (pinfunction "2_2") (pintype "passive"))
      (node (ref "C27") (pin "1") (pinfunction "1_1") (pintype "passive"))
      (node (ref "C28") (pin "2") (pinfunction "2_2") (pintype "passive"))
      (node (ref "C29") (pin "2") (pinfunction "2_2") (pintype "passive"))
      (node (ref "C3") (pin "+") (pinfunction "+_+") (pintype "passive"))
      (node (ref "C38") (pin "1") (pinfunction "1_1") (pintype "passive"))
      (node (ref "C39") (pin "1") (pinfunction "1_1") (pintype "passive"))
      (node (ref "C4") (pin "-") (pinfunction "-_-") (pintype "passive"))
      (node (ref "C40") (pin "2") (pinfunction "2_2") (pintype "passive"))
      (node (ref "C41") (pin "2") (pinfunction "2_2") (pintype "passive"))
      (node (ref "C43") (pin "2") (pinfunction "2_2") (pintype "passive"))
      (node (ref "C47") (pin "2") (pinfunction "2_2") (pintype "passive"))
      (node (ref "C48") (pin "1") (pinfunction "1_1") (pintype "passive"))
      (node (ref "C49") (pin "2") (pinfunction "2_2") (pintype "passive"))
      (node (ref "C5") (pin "-") (pinfunction "-_-") (pintype "passive"))
      (node (ref "C50") (pin "1") (pinfunction "1_1") (pintype "passive"))
      (node (ref "C57") (pin "2") (pinfunction "2_2") (pintype "passive"))
      (node (ref "C58") (pin "1") (pinfunction "1_1") (pintype "passive"))
      (node (ref "C6") (pin "+") (pinfunction "+_+") (pintype "passive"))
      (node (ref "C7") (pin "1") (pinfunction "1_1") (pintype "passive"))
      (node (ref "C8") (pin "2") (pinfunction "2_2") (pintype "passive"))
      (node (ref "IC5") (pin "TAB") (pinfunction "GND_TAB") (pintype "passive"))
      (node (ref "IC6") (pin "1") (pinfunction "GND_1") (pintype "passive"))
      (node (ref "JP12") (pin "2") (pinfunction "2_2") (pintype "passive"))
      (node (ref "JP2") (pin "2") (pinfunction "2_2") (pintype "passive"))
      (node (ref "JP4") (pin "2") (pinfunction "2_2") (pintype "passive"))
      (node (ref "JP5") (pin "2") (pinfunction "2_2") (pintype "passive"))
      (node (ref "Q2") (pin "2") (pinfunction "S_2") (pintype "passive"))
      (node (ref "R12") (pin "1") (pinfunction "1_1") (pintype "passive"))
      (node (ref "R18") (pin "2") (pinfunction "2_2") (pintype "passive"))
      (node (ref "R20") (pin "1") (pinfunction "1_1") (pintype "passive"))
      (node (ref "R26") (pin "1") (pinfunction "1_1") (pintype "passive"))
      (node (ref "R3") (pin "1") (pinfunction "A_1") (pintype "passive"))
      (node (ref "R33") (pin "2") (pinfunction "2_2") (pintype "passive"))
      (node (ref "R4") (pin "2") (pinfunction "2_2") (pintype "passive"))
      (node (ref "R51") (pin "1") (pinfunction "1_1") (pintype "passive"))
      (node (ref "R68") (pin "1") (pinfunction "1_1") (pintype "passive"))
      (node (ref "R69") (pin "1") (pinfunction "1_1") (pintype "passive"))
      (node (ref "R70") (pin "1") (pinfunction "1_1") (pintype "passive"))
      (node (ref "T1") (pin "C") (pinfunction "C_C") (pintype "passive"))
      (node (ref "V+") (pin "C") (pinfunction "C_C") (pintype "passive"))
      (node (ref "V-") (pin "A") (pinfunction "A_A") (pintype "passive"))
      (node (ref "X1") (pin "GND1") (pinfunction "GND1_GND1") (pintype "power_in"))
      (node (ref "X1") (pin "GND2") (pinfunction "GND2_GND2") (pintype "power_in"))
      (node (ref "X1") (pin "GND3") (pinfunction "GND3_GND3") (pintype "power_in"))
      (node (ref "X1") (pin "GND4") (pinfunction "GND4_GND4") (pintype "power_in"))
      (node (ref "X2") (pin "GND1") (pinfunction "GND1_GND1") (pintype "power_in"))
      (node (ref "X2") (pin "GND2") (pinfunction "GND2_GND2") (pintype "power_in"))
      (node (ref "X2") (pin "GND3") (pinfunction "GND3_GND3") (pintype "power_in"))
      (node (ref "X2") (pin "GND4") (pinfunction "GND4_GND4") (pintype "power_in"))
    )
    (net (code "18") (name "MOSI_DAC") (class "Default")
      (node (ref "R40") (pin "1") (pinfunction "1_1") (pintype "passive"))
      (node (ref "U1") (pin "22") (pinfunction "PA13(I2C/SER2:1+)_22") (pintype "bidirectional"))
    )
    (net (code "19") (name "Net-(C9-Pad-)") (class "Default")
      (node (ref "C9") (pin "-") (pinfunction "-_-") (pintype "passive"))
      (node (ref "R5") (pin "2") (pinfunction "2_2") (pintype "passive"))
      (node (ref "R6") (pin "1") (pinfunction "1_1") (pintype "passive"))
    )
    (net (code "20") (name "Net-(C11-Pad2)") (class "Default")
      (node (ref "C11") (pin "2") (pinfunction "2_2") (pintype "passive"))
      (node (ref "R9") (pin "2") (pinfunction "2_2") (pintype "passive"))
    )
    (net (code "21") (name "Net-(C14-Pad1)") (class "Default")
      (node (ref "C14") (pin "1") (pinfunction "1_1") (pintype "passive"))
      (node (ref "D2") (pin "A") (pinfunction "A_A") (pintype "passive"))
      (node (ref "R2") (pin "1") (pinfunction "1_1") (pintype "passive"))
      (node (ref "T1") (pin "B") (pinfunction "B_B") (pintype "passive"))
    )
    (net (code "22") (name "Net-(C28-Pad1)") (class "Default")
      (node (ref "C28") (pin "1") (pinfunction "1_1") (pintype "passive"))
      (node (ref "JP1") (pin "2") (pinfunction "2_2") (pintype "passive"))
      (node (ref "R24") (pin "1") (pinfunction "1_1") (pintype "passive"))
    )
    (net (code "23") (name "Net-(IC1-ADJ)") (class "Default")
      (node (ref "C13") (pin "1") (pinfunction "1_1") (pintype "passive"))
      (node (ref "IC1") (pin "1") (pinfunction "ADJ_1") (pintype "input"))
      (node (ref "IC4") (pin "1") (pinfunction "ADJ_1") (pintype "input"))
      (node (ref "R1") (pin "2") (pinfunction "2_2") (pintype "passive"))
      (node (ref "R2") (pin "2") (pinfunction "2_2") (pintype "passive"))
      (node (ref "R3") (pin "2") (pinfunction "S_2") (pintype "passive"))
      (node (ref "R3") (pin "3") (pinfunction "E_3") (pintype "passive"))
      (node (ref "T1") (pin "E") (pinfunction "E_E") (pintype "passive"))
    )
    (net (code "24") (name "Net-(IC1-IN)") (class "Default")
      (node (ref "C1") (pin "1") (pinfunction "1_1") (pintype "passive"))
      (node (ref "C2") (pin "1") (pinfunction "1_1") (pintype "passive"))
      (node (ref "D1") (pin "C") (pinfunction "C_C") (pintype "passive"))
      (node (ref "D4") (pin "C") (pinfunction "C_C") (pintype "passive"))
      (node (ref "IC1") (pin "3") (pinfunction "IN_3") (pintype "input"))
      (node (ref "IC4") (pin "3") (pinfunction "IN_3") (pintype "input"))
      (node (ref "R7") (pin "2") (pinfunction "2_2") (pintype "passive"))
    )
    (net (code "25") (name "Net-(IC1-OUT)") (class "Default")
      (node (ref "C15") (pin "1") (pinfunction "1_1") (pintype "passive"))
      (node (ref "D1") (pin "A") (pinfunction "A_A") (pintype "passive"))
      (node (ref "D2") (pin "C") (pinfunction "C_C") (pintype "passive"))
      (node (ref "IC1") (pin "4") (pinfunction "OUT_4") (pintype "passive"))
      (node (ref "IC4") (pin "2") (pinfunction "OUT_2") (pintype "passive"))
      (node (ref "R1") (pin "1") (pinfunction "1_1") (pintype "passive"))
      (node (ref "R11") (pin "1") (pinfunction "1_1") (pintype "passive"))
    )
    (net (code "26") (name "Net-(IC2-Pad2)") (class "Default")
      (node (ref "IC2") (pin "2") (pinfunction "2_2") (pintype "input"))
      (node (ref "R28") (pin "2") (pinfunction "2_2") (pintype "passive"))
      (node (ref "R8") (pin "1") (pinfunction "1_1") (pintype "passive"))
    )
    (net (code "27") (name "Net-(IC3A-+IN)") (class "Default")
      (node (ref "C17") (pin "1") (pinfunction "1_1") (pintype "passive"))
      (node (ref "IC3") (pin "3") (pinfunction "+IN_3") (pintype "input"))
      (node (ref "JP4") (pin "1") (pinfunction "1_1") (pintype "passive"))
      (node (ref "L3") (pin "2") (pinfunction "2_2") (pintype "passive"))
      (node (ref "R15") (pin "2") (pinfunction "2_2") (pintype "passive"))
      (node (ref "R16") (pin "1") (pinfunction "1_1") (pintype "passive"))
    )
    (net (code "28") (name "Net-(IC3A--IN)") (class "Default")
      (node (ref "IC3") (pin "2") (pinfunction "-IN_2") (pintype "input"))
      (node (ref "R12") (pin "2") (pinfunction "2_2") (pintype "passive"))
      (node (ref "R13") (pin "1") (pinfunction "1_1") (pintype "passive"))
    )
    (net (code "29") (name "Net-(IC3A-OUT)") (class "Default")
      (node (ref "IC3") (pin "1") (pinfunction "OUT_1") (pintype "output"))
      (node (ref "R13") (pin "2") (pinfunction "2_2") (pintype "passive"))
      (node (ref "R14") (pin "1") (pinfunction "1_1") (pintype "passive"))
      (node (ref "R15") (pin "1") (pinfunction "1_1") (pintype "passive"))
    )
    (net (code "30") (name "Net-(IC3B-+IN)") (class "Default")
      (node (ref "IC3") (pin "5") (pinfunction "+IN_5") (pintype "input"))
      (node (ref "R18") (pin "1") (pinfunction "1_1") (pintype "passive"))
    )
    (net (code "31") (name "Net-(IC3B--IN)") (class "Default")
      (node (ref "C12") (pin "1") (pinfunction "1_1") (pintype "passive"))
      (node (ref "IC3") (pin "6") (pinfunction "-IN_6") (pintype "input"))
      (node (ref "R14") (pin "2") (pinfunction "2_2") (pintype "passive"))
      (node (ref "R19") (pin "1") (pinfunction "1_1") (pintype "passive"))
    )
    (net (code "32") (name "Net-(IC3B-OUT)") (class "Default")
      (node (ref "C12") (pin "2") (pinfunction "2_2") (pintype "passive"))
      (node (ref "IC3") (pin "7") (pinfunction "OUT_7") (pintype "output"))
      (node (ref "R17") (pin "2") (pinfunction "2_2") (pintype "passive"))
      (node (ref "R19") (pin "2") (pinfunction "2_2") (pintype "passive"))
    )
    (net (code "33") (name "Net-(IC7A-IN+)") (class "Default")
      (node (ref "IC7") (pin "3") (pinfunction "IN+_3") (pintype "input"))
      (node (ref "R27") (pin "2") (pinfunction "2_2") (pintype "passive"))
      (node (ref "R28") (pin "1") (pinfunction "1_1") (pintype "passive"))
    )
    (net (code "34") (name "Net-(IC7B-IN+)") (class "Default")
      (node (ref "C10") (pin "-") (pinfunction "-_-") (pintype "passive"))
      (node (ref "IC7") (pin "5") (pinfunction "IN+_5") (pintype "input"))
      (node (ref "R6") (pin "2") (pinfunction "2_2") (pintype "passive"))
    )
    (net (code "35") (name "Net-(IC7B-IN-)") (class "Default")
      (node (ref "IC7") (pin "6") (pinfunction "IN-_6") (pintype "input"))
      (node (ref "IC9") (pin "3") (pinfunction "IN+_3") (pintype "input"))
      (node (ref "Q1") (pin "S") (pinfunction "S_S") (pintype "passive"))
      (node (ref "RA1") (pin "1") (pinfunction "1_1") (pintype "passive"))
      (node (ref "RA2") (pin "1") (pinfunction "1_1") (pintype "passive"))
    )
    (net (code "36") (name "Net-(IC7B-OUT)") (class "Default")
      (node (ref "IC7") (pin "7") (pinfunction "OUT_7") (pintype "output"))
      (node (ref "R10") (pin "2") (pinfunction "2_2") (pintype "passive"))
    )
    (net (code "37") (name "Net-(IC8-+IN)") (class "Default")
      (node (ref "IC8") (pin "3") (pinfunction "+IN_3") (pintype "input"))
      (node (ref "R64") (pin "2") (pinfunction "2_2") (pintype "passive"))
      (node (ref "R65") (pin "1") (pinfunction "1_1") (pintype "passive"))
    )
    (net (code "38") (name "Net-(IC8--IN)") (class "Default")
      (node (ref "IC8") (pin "2") (pinfunction "-IN_2") (pintype "input"))
      (node (ref "R66") (pin "2") (pinfunction "2_2") (pintype "passive"))
      (node (ref "R67") (pin "1") (pinfunction "1_1") (pintype "passive"))
    )
    (net (code "39") (name "Net-(IC9A-IN-)") (class "Default")
      (node (ref "IC9") (pin "1") (pinfunction "OUT_1") (pintype "output"))
      (node (ref "IC9") (pin "2") (pinfunction "IN-_2") (pintype "input"))
      (node (ref "R49") (pin "2") (pinfunction "2_2") (pintype "passive"))
    )
    (net (code "40") (name "Net-(IC9B-IN+)") (class "Default")
      (node (ref "IC9") (pin "5") (pinfunction "IN+_5") (pintype "input"))
      (node (ref "R48") (pin "1") (pinfunction "1_1") (pintype "passive"))
      (node (ref "R51") (pin "2") (pinfunction "2_2") (pintype "passive"))
    )
    (net (code "41") (name "Net-(IC9B-IN-)") (class "Default")
      (node (ref "IC9") (pin "6") (pinfunction "IN-_6") (pintype "input"))
      (node (ref "R49") (pin "1") (pinfunction "1_1") (pintype "passive"))
      (node (ref "R50") (pin "2") (pinfunction "2_2") (pintype "passive"))
    )
    (net (code "42") (name "Net-(IC9B-OUT)") (class "Default")
      (node (ref "IC9") (pin "7") (pinfunction "OUT_7") (pintype "output"))
      (node (ref "R50") (pin "1") (pinfunction "1_1") (pintype "passive"))
      (node (ref "RMON") (pin "2") (pinfunction "2_2") (pintype "passive"))
    )
    (net (code "43") (name "Net-(IC10A-O)") (class "Default")
      (node (ref "IC10") (pin "4") (pinfunction "O_4") (pintype "tri_state"))
      (node (ref "R60") (pin "1") (pinfunction "1_1") (pintype "passive"))
      (node (ref "R61") (pin "2") (pinfunction "2_2") (pintype "passive"))
      (node (ref "TR1") (pin "3") (pinfunction "G_3") (pintype "passive"))
    )
    (net (code "44") (name "Net-(JP5-Pad1)") (class "Default")
      (node (ref "JP5") (pin "1") (pinfunction "1_1") (pintype "passive"))
      (node (ref "R7") (pin "1") (pinfunction "1_1") (pintype "passive"))
    )
    (net (code "45") (name "Net-(JP7-Pad2)") (class "Default")
      (node (ref "JP7") (pin "2") (pinfunction "2_2") (pintype "passive"))
      (node (ref "R42") (pin "2") (pinfunction "2_2") (pintype "passive"))
      (node (ref "R45") (pin "1") (pinfunction "1_1") (pintype "passive"))
    )
    (net (code "46") (name "Net-(JP7-Pad4)") (class "Default")
      (node (ref "JP7") (pin "4") (pinfunction "4_4") (pintype "passive"))
      (node (ref "R43") (pin "2") (pinfunction "2_2") (pintype "passive"))
      (node (ref "R44") (pin "1") (pinfunction "1_1") (pintype "passive"))
    )
    (net (code "47") (name "Net-(JP7-Pad5)") (class "Default")
      (node (ref "JP7") (pin "5") (pinfunction "5_5") (pintype "passive"))
      (node (ref "R46") (pin "2") (pinfunction "2_2") (pintype "passive"))
      (node (ref "R47") (pin "2") (pinfunction "2_2") (pintype "passive"))
    )
    (net (code "48") (name "Net-(L3-Pad1)") (class "Default")
      (node (ref "L3") (pin "1") (pinfunction "1_1") (pintype "passive"))
      (node (ref "Q1") (pin "D") (pinfunction "D_D") (pintype "passive"))
    )
    (net (code "49") (name "Net-(Q1-PadG)") (class "Default")
      (node (ref "Q1") (pin "G") (pinfunction "G_G") (pintype "passive"))
      (node (ref "R10") (pin "1") (pinfunction "1_1") (pintype "passive"))
      (node (ref "R9") (pin "1") (pinfunction "1_1") (pintype "passive"))
    )
    (net (code "50") (name "Net-(Q2-D)") (class "Default")
      (node (ref "C42") (pin "2") (pinfunction "2_2") (pintype "passive"))
      (node (ref "Q2") (pin "3") (pinfunction "D_3") (pintype "passive"))
      (node (ref "Q3") (pin "1") (pinfunction "G_1") (pintype "passive"))
      (node (ref "R23") (pin "1") (pinfunction "1_1") (pintype "passive"))
      (node (ref "R24") (pin "2") (pinfunction "2_2") (pintype "passive"))
    )
    (net (code "51") (name "Net-(Q2-G)") (class "Default")
      (node (ref "C43") (pin "1") (pinfunction "1_1") (pintype "passive"))
      (node (ref "JP1") (pin "1") (pinfunction "1_1") (pintype "passive"))
      (node (ref "Q2") (pin "1") (pinfunction "G_1") (pintype "passive"))
      (node (ref "R25") (pin "1") (pinfunction "1_1") (pintype "passive"))
    )
    (net (code "52") (name "Net-(Q3-D)") (class "Default")
      (node (ref "D4") (pin "A") (pinfunction "A_A") (pintype "passive"))
      (node (ref "Q3") (pin "3") (pinfunction "D_3") (pintype "passive"))
      (node (ref "R25") (pin "2") (pinfunction "2_2") (pintype "passive"))
      (node (ref "R26") (pin "2") (pinfunction "2_2") (pintype "passive"))
    )
    (net (code "53") (name "Net-(R21-Pad1)") (class "Default")
      (node (ref "R21") (pin "1") (pinfunction "1_1") (pintype "passive"))
      (node (ref "V-") (pin "C") (pinfunction "C_C") (pintype "passive"))
    )
    (net (code "54") (name "Net-(R22-Pad1)") (class "Default")
      (node (ref "R22") (pin "1") (pinfunction "1_1") (pintype "passive"))
      (node (ref "V+") (pin "A") (pinfunction "A_A") (pintype "passive"))
    )
    (net (code "55") (name "Net-(R66-Pad1)") (class "Default")
      (node (ref "R66") (pin "1") (pinfunction "1_1") (pintype "passive"))
      (node (ref "X3") (pin "GND1") (pinfunction "GND1_GND1") (pintype "power_in"))
      (node (ref "X3") (pin "GND2") (pinfunction "GND2_GND2") (pintype "power_in"))
      (node (ref "X3") (pin "GND3") (pinfunction "GND3_GND3") (pintype "power_in"))
      (node (ref "X3") (pin "GND4") (pinfunction "GND4_GND4") (pintype "power_in"))
    )
    (net (code "56") (name "Net-(U1-PA00(XIN32{slash}SER1:0{slash}TC2:0))") (class "Default")
      (node (ref "C55") (pin "2") (pinfunction "2_2") (pintype "passive"))
      (node (ref "U1") (pin "1") (pinfunction "PA00(XIN32/SER1:0/TC2:0)_1") (pintype "bidirectional"))
      (node (ref "Y1") (pin "P$2") (pinfunction "2_P$2") (pintype "bidirectional"))
    )
    (net (code "57") (name "Net-(U1-PA01(XOUT32{slash}SER1:1{slash}TC2:1))") (class "Default")
      (node (ref "C56") (pin "2") (pinfunction "2_2") (pintype "passive"))
      (node (ref "U1") (pin "2") (pinfunction "PA01(XOUT32/SER1:1/TC2:1)_2") (pintype "bidirectional"))
      (node (ref "Y1") (pin "P$1") (pinfunction "1_P$1") (pintype "bidirectional"))
    )
    (net (code "58") (name "Net-(U1-PA19(SER1:3+))") (class "Default")
      (node (ref "JP10") (pin "1") (pinfunction "1_1") (pintype "passive"))
      (node (ref "U1") (pin "28") (pinfunction "PA19(SER1:3+)_28") (pintype "bidirectional"))
    )
    (net (code "59") (name "Net-(U1-PA20(SER5:2+))") (class "Default")
      (node (ref "JP10") (pin "2") (pinfunction "2_2") (pintype "passive"))
      (node (ref "U1") (pin "29") (pinfunction "PA20(SER5:2+)_29") (pintype "bidirectional"))
    )
    (net (code "60") (name "Net-(U1-PA21(SER5:3+))") (class "Default")
      (node (ref "JP10") (pin "3") (pinfunction "3_3") (pintype "passive"))
      (node (ref "U1") (pin "30") (pinfunction "PA21(SER5:3+)_30") (pintype "bidirectional"))
    )
    (net (code "61") (name "Net-(U1-VDDANA)") (class "Default")
      (node (ref "C54") (pin "1") (pinfunction "1_1") (pintype "passive"))
      (node (ref "L4") (pin "1") (pinfunction "1_1") (pintype "passive"))
      (node (ref "U1") (pin "6") (pinfunction "VDDANA_6") (pintype "bidirectional"))
    )
    (net (code "62") (name "Net-(U3-VOUT)") (class "Default")
      (node (ref "R5") (pin "1") (pinfunction "1_1") (pintype "passive"))
      (node (ref "U3") (pin "1") (pinfunction "VOUT_1") (pintype "bidirectional"))
    )
    (net (code "63") (name "Net-(U4-NEG1)") (class "Default")
      (node (ref "R29") (pin "2") (pinfunction "2_2") (pintype "passive"))
      (node (ref "R35") (pin "1") (pinfunction "1_1") (pintype "passive"))
      (node (ref "U4") (pin "2") (pinfunction "NEG1_2") (pintype "input"))
    )
    (net (code "64") (name "Net-(U4-NEG2)") (class "Default")
      (node (ref "R31") (pin "2") (pinfunction "2_2") (pintype "passive"))
      (node (ref "R34") (pin "1") (pinfunction "1_1") (pintype "passive"))
      (node (ref "U4") (pin "6") (pinfunction "NEG2_6") (pintype "input"))
    )
    (net (code "65") (name "Net-(U4-NEG3)") (class "Default")
      (node (ref "R32") (pin "2") (pinfunction "2_2") (pintype "passive"))
      (node (ref "R33") (pin "1") (pinfunction "1_1") (pintype "passive"))
      (node (ref "U4") (pin "9") (pinfunction "NEG3_9") (pintype "input"))
    )
    (net (code "66") (name "Net-(U4-NEG4)") (class "Default")
      (node (ref "R52") (pin "2") (pinfunction "2_2") (pintype "passive"))
      (node (ref "R53") (pin "1") (pinfunction "1_1") (pintype "passive"))
      (node (ref "U4") (pin "13") (pinfunction "NEG4_13") (pintype "input"))
    )
    (net (code "67") (name "Net-(U4-POS1)") (class "Default")
      (node (ref "R36") (pin "1") (pinfunction "1_1") (pintype "passive"))
      (node (ref "R39") (pin "2") (pinfunction "2_2") (pintype "passive"))
      (node (ref "U4") (pin "3") (pinfunction "POS1_3") (pintype "input"))
    )
    (net (code "68") (name "Net-(U4-POS2)") (class "Default")
      (node (ref "R37") (pin "1") (pinfunction "1_1") (pintype "passive"))
      (node (ref "R40") (pin "2") (pinfunction "2_2") (pintype "passive"))
      (node (ref "U4") (pin "5") (pinfunction "POS2_5") (pintype "input"))
    )
    (net (code "69") (name "Net-(U4-POS3)") (class "Default")
      (node (ref "R54") (pin "1") (pinfunction "1_1") (pintype "passive"))
      (node (ref "R55") (pin "2") (pinfunction "2_2") (pintype "passive"))
      (node (ref "U4") (pin "10") (pinfunction "POS3_10") (pintype "input"))
    )
    (net (code "70") (name "Net-(U4-POS4)") (class "Default")
      (node (ref "R38") (pin "1") (pinfunction "1_1") (pintype "passive"))
      (node (ref "R41") (pin "2") (pinfunction "2_2") (pintype "passive"))
      (node (ref "U4") (pin "12") (pinfunction "POS4_12") (pintype "input"))
    )
    (net (code "71") (name "Net-(X1-ANT)") (class "Default")
      (node (ref "R16") (pin "2") (pinfunction "2_2") (pintype "passive"))
      (node (ref "R17") (pin "1") (pinfunction "1_1") (pintype "passive"))
      (node (ref "R4") (pin "1") (pinfunction "1_1") (pintype "passive"))
      (node (ref "X1") (pin "ANTENNA") (pinfunction "ANT_ANTENNA") (pintype "bidirectional"))
    )
    (net (code "72") (name "Net-(X2-ANT)") (class "Default")
      (node (ref "C17") (pin "2") (pinfunction "2_2") (pintype "passive"))
      (node (ref "R20") (pin "2") (pinfunction "2_2") (pintype "passive"))
      (node (ref "X2") (pin "ANTENNA") (pinfunction "ANT_ANTENNA") (pintype "bidirectional"))
    )
    (net (code "73") (name "Net-(X3-ANT)") (class "Default")
      (node (ref "R64") (pin "1") (pinfunction "1_1") (pintype "passive"))
      (node (ref "X3") (pin "ANTENNA") (pinfunction "ANT_ANTENNA") (pintype "bidirectional"))
    )
    (net (code "74") (name "PA02_AIN0") (class "Default")
      (node (ref "U1") (pin "3") (pinfunction "PA02(AIN0/DAC)_3") (pintype "bidirectional"))
    )
    (net (code "75") (name "PA04_AIN4") (class "Default")
      (node (ref "JP8") (pin "2") (pinfunction "2_2") (pintype "passive"))
      (node (ref "U1") (pin "9") (pinfunction "PA04(AIN4/REFB/SER0:0/TC0:0)_9") (pintype "bidirectional"))
    )
    (net (code "76") (name "PA05_AIN5") (class "Default")
      (node (ref "JP8") (pin "1") (pinfunction "1_1") (pintype "passive"))
      (node (ref "U1") (pin "10") (pinfunction "PA05(AIN5/SER0:1/TC0:1)_10") (pintype "bidirectional"))
    )
    (net (code "77") (name "PA28_USB_HOST_EN") (class "Default")
      (node (ref "R63") (pin "1") (pinfunction "1_1") (pintype "passive"))
      (node (ref "U1") (pin "41") (pinfunction "PA28_41") (pintype "bidirectional"))
    )
    (net (code "78") (name "PB10_S4_SPI_MOSI") (class "Default")
      (node (ref "U1") (pin "19") (pinfunction "PB10(SER4:2+)_19") (pintype "bidirectional"))
    )
    (net (code "79") (name "PB11_S4_SPI_SCK") (class "Default")
      (node (ref "U1") (pin "20") (pinfunction "PB11(SER4:3+)_20") (pintype "bidirectional"))
    )
    (net (code "80") (name "PB12_S4_SPI_MISO") (class "Default")
      (node (ref "U1") (pin "21") (pinfunction "PA12(I2C/SER2:0+)_21") (pintype "bidirectional"))
    )
    (net (code "81") (name "RESET") (class "Default")
      (node (ref "J1") (pin "10") (pinfunction "~{RESET}_10") (pintype "bidirectional"))
      (node (ref "R30") (pin "1") (pinfunction "1_1") (pintype "passive"))
      (node (ref "R56") (pin "1") (pinfunction "1_1") (pintype "passive"))
      (node (ref "S1") (pin "3") (pinfunction "2_3") (pintype "passive"))
    )
    (net (code "82") (name "SCK_DAC") (class "Default")
      (node (ref "R39") (pin "1") (pinfunction "1_1") (pintype "passive"))
      (node (ref "U1") (pin "23") (pinfunction "PA14(XIN/SER2:2+)_23") (pintype "bidirectional"))
    )
    (net (code "83") (name "SCL") (class "Default")
      (node (ref "JP3") (pin "7") (pinfunction "7_7") (pintype "passive"))
      (node (ref "JP3") (pin "8") (pinfunction "8_8") (pintype "passive"))
      (node (ref "R58") (pin "1") (pinfunction "1_1") (pintype "passive"))
      (node (ref "U1") (pin "32") (pinfunction "PA23(I2C/SER3:0+)_32") (pintype "bidirectional"))
    )
    (net (code "84") (name "SDA") (class "Default")
      (node (ref "JP3") (pin "5") (pinfunction "5_5") (pintype "passive"))
      (node (ref "JP3") (pin "6") (pinfunction "6_6") (pintype "passive"))
      (node (ref "R57") (pin "1") (pinfunction "1_1") (pintype "passive"))
      (node (ref "U1") (pin "31") (pinfunction "PA22(I2C/SER3:0+)_31") (pintype "bidirectional"))
    )
    (net (code "85") (name "SWDCLK") (class "Default")
      (node (ref "J1") (pin "4") (pinfunction "SWDCLK/TCK_4") (pintype "bidirectional"))
      (node (ref "U1") (pin "45") (pinfunction "PA30(SWCLK/SER1:2+)_45") (pintype "bidirectional"))
    )
    (net (code "86") (name "SWDIO") (class "Default")
      (node (ref "J1") (pin "2") (pinfunction "SWDIO/TMS_2") (pintype "bidirectional"))
      (node (ref "U1") (pin "46") (pinfunction "PA31(SWDIO/SER1:3+)_46") (pintype "bidirectional"))
    )
    (net (code "87") (name "TARGET_RESET") (class "Default")
      (node (ref "C23") (pin "1") (pinfunction "1_1") (pintype "passive"))
      (node (ref "R56") (pin "2") (pinfunction "2_2") (pintype "passive"))
      (node (ref "U1") (pin "40") (pinfunction "~{RESET}_40") (pintype "bidirectional"))
    )
    (net (code "88") (name "TARGET_USB_N") (class "Default")
      (node (ref "U1") (pin "33") (pinfunction "PA24(SER3:2+)_33") (pintype "bidirectional"))
      (node (ref "USB") (pin "D-") (pinfunction "D-_D-") (pintype "bidirectional"))
    )
    (net (code "89") (name "TARGET_USB_P") (class "Default")
      (node (ref "U1") (pin "34") (pinfunction "PA25(SER3:3+)_34") (pintype "bidirectional"))
      (node (ref "USB") (pin "D+") (pinfunction "D+_D+") (pintype "bidirectional"))
    )
    (net (code "90") (name "USBVCC") (class "Default")
      (node (ref "C36") (pin "2") (pinfunction "2_2") (pintype "passive"))
      (node (ref "F1") (pin "2") (pinfunction "2_2") (pintype "passive"))
      (node (ref "R59") (pin "2") (pinfunction "2_2") (pintype "passive"))
      (node (ref "TR1") (pin "1") (pinfunction "D_1") (pintype "passive"))
    )
    (net (code "91") (name "USB_ID") (class "Default")
      (node (ref "IC10") (pin "1") (pinfunction "OE_1") (pintype "input"))
      (node (ref "IC10") (pin "2") (pinfunction "I_2") (pintype "input"))
      (node (ref "R62") (pin "1") (pinfunction "1_1") (pintype "passive"))
      (node (ref "R63") (pin "2") (pinfunction "2_2") (pintype "passive"))
      (node (ref "USB") (pin "ID") (pinfunction "ID_ID") (pintype "bidirectional"))
    )
    (net (code "92") (name "V+") (class "Default")
      (node (ref "C5") (pin "+") (pinfunction "+_+") (pintype "passive"))
      (node (ref "IC5") (pin "1") (pinfunction "VI_1") (pintype "input"))
      (node (ref "JP12") (pin "1") (pinfunction "1_1") (pintype "passive"))
      (node (ref "L1") (pin "2") (pinfunction "2_2") (pintype "passive"))
      (node (ref "R22") (pin "2") (pinfunction "2_2") (pintype "passive"))
      (node (ref "TP1") (pin "P$1") (pinfunction "1_P$1") (pintype "bidirectional"))
    )
    (net (code "93") (name "V-") (class "Default")
      (node (ref "C6") (pin "-") (pinfunction "-_-") (pintype "passive"))
      (node (ref "IC6") (pin "TAB") (pinfunction "VI_TAB") (pintype "input"))
      (node (ref "L2") (pin "1") (pinfunction "1_1") (pintype "passive"))
      (node (ref "R21") (pin "2") (pinfunction "2_2") (pintype "passive"))
      (node (ref "TP2") (pin "P$1") (pinfunction "1_P$1") (pintype "bidirectional"))
    )
    (net (code "94") (name "VCCINT") (class "Default")
      (node (ref "C10") (pin "+") (pinfunction "+_+") (pintype "passive"))
      (node (ref "C11") (pin "1") (pinfunction "1_1") (pintype "passive"))
      (node (ref "C16") (pin "1") (pinfunction "1_1") (pintype "passive"))
      (node (ref "C29") (pin "1") (pinfunction "1_1") (pintype "passive"))
      (node (ref "C30") (pin "1") (pinfunction "1_1") (pintype "passive"))
      (node (ref "C31") (pin "1") (pinfunction "1_1") (pintype "passive"))
      (node (ref "C32") (pin "1") (pinfunction "1_1") (pintype "passive"))
      (node (ref "C9") (pin "+") (pinfunction "+_+") (pintype "passive"))
      (node (ref "IC2") (pin "1") (pinfunction "1_1") (pintype "input"))
      (node (ref "R11") (pin "2") (pinfunction "2_2") (pintype "passive"))
      (node (ref "R27") (pin "1") (pinfunction "1_1") (pintype "passive"))
      (node (ref "R48") (pin "2") (pinfunction "2_2") (pintype "passive"))
      (node (ref "RA1") (pin "2") (pinfunction "2_2") (pintype "passive"))
      (node (ref "RA2") (pin "2") (pinfunction "2_2") (pintype "passive"))
      (node (ref "U3") (pin "3") (pinfunction "REF_3") (pintype "bidirectional"))
      (node (ref "U3") (pin "8") (pinfunction "VDD_8") (pintype "bidirectional"))
    )
    (net (code "95") (name "VDDCORE") (class "Default")
      (node (ref "C53") (pin "1") (pinfunction "1_1") (pintype "passive"))
      (node (ref "U1") (pin "43") (pinfunction "VDDCORE_43") (pintype "bidirectional"))
    )
    (net (code "96") (name "VIN") (class "Default")
      (node (ref "IC8") (pin "6") (pinfunction "OUT_6") (pintype "output"))
      (node (ref "R67") (pin "2") (pinfunction "2_2") (pintype "passive"))
      (node (ref "U1") (pin "47") (pinfunction "PB02(AIN10/SER5:0)_47") (pintype "bidirectional"))
    )
    (net (code "97") (name "VMON") (class "Default")
      (node (ref "R55") (pin "1") (pinfunction "1_1") (pintype "passive"))
      (node (ref "RMON") (pin "1") (pinfunction "1_1") (pintype "passive"))
    )
    (net (code "98") (name "XUSB") (class "Default")
      (node (ref "C35") (pin "1") (pinfunction "1_1") (pintype "passive"))
      (node (ref "F1") (pin "1") (pinfunction "1_1") (pintype "passive"))
      (node (ref "USB") (pin "VBUS") (pinfunction "VBUS_VBUS") (pintype "power_in"))
    )
    (net (code "99") (name "unconnected-(IC8-ON1-Pad1)") (class "Default")
      (node (ref "IC8") (pin "1") (pinfunction "ON1_1") (pintype "passive"))
    )
    (net (code "100") (name "unconnected-(IC8-ON2-Pad5)") (class "Default")
      (node (ref "IC8") (pin "5") (pinfunction "ON2_5") (pintype "passive"))
    )
    (net (code "101") (name "unconnected-(IC8-OPT-Pad8)") (class "Default")
      (node (ref "IC8") (pin "8") (pinfunction "OPT_8") (pintype "passive"))
    )
    (net (code "102") (name "unconnected-(J1-GNDDTCT-Pad9)") (class "Default")
      (node (ref "J1") (pin "9") (pinfunction "GNDDTCT_9") (pintype "bidirectional"))
    )
    (net (code "103") (name "unconnected-(J1-KEY-Pad7)") (class "Default")
      (node (ref "J1") (pin "7") (pinfunction "KEY_7") (pintype "bidirectional"))
    )
    (net (code "104") (name "unconnected-(J1-NC{slash}TDI-Pad8)") (class "Default")
      (node (ref "J1") (pin "8") (pinfunction "NC/TDI_8") (pintype "bidirectional"))
    )
    (net (code "105") (name "unconnected-(J1-SWO{slash}TDO-Pad6)") (class "Default")
      (node (ref "J1") (pin "6") (pinfunction "SWO/TDO_6") (pintype "bidirectional"))
    )
    (net (code "106") (name "unconnected-(U1-PA03(AIN1{slash}REFA)-Pad4)") (class "Default")
      (node (ref "U1") (pin "4") (pinfunction "PA03(AIN1/REFA)_4") (pintype "bidirectional"))
    )
    (net (code "107") (name "unconnected-(U1-PA06(AIN6{slash}SER0:2{slash}TC1:0)-Pad11)") (class "Default")
      (node (ref "U1") (pin "11") (pinfunction "PA06(AIN6/SER0:2/TC1:0)_11") (pintype "bidirectional"))
    )
    (net (code "108") (name "unconnected-(U1-PA07(AIN7{slash}SER0:3{slash}TC1:1)-Pad12)") (class "Default")
      (node (ref "U1") (pin "12") (pinfunction "PA07(AIN7/SER0:3/TC1:1)_12") (pintype "bidirectional"))
    )
    (net (code "109") (name "unconnected-(U1-PA11(AIN19{slash}SER0:3+)-Pad16)") (class "Default")
      (node (ref "U1") (pin "16") (pinfunction "PA11(AIN19/SER0:3+)_16") (pintype "bidirectional"))
    )
    (net (code "110") (name "unconnected-(U1-PA16(I2C{slash}SER1:0+)-Pad25)") (class "Default")
      (node (ref "U1") (pin "25") (pinfunction "PA16(I2C/SER1:0+)_25") (pintype "bidirectional"))
    )
    (net (code "111") (name "unconnected-(U1-PA17(I2C{slash}SER1:1+)-Pad26)") (class "Default")
      (node (ref "U1") (pin "26") (pinfunction "PA17(I2C/SER1:1+)_26") (pintype "bidirectional"))
    )
    (net (code "112") (name "unconnected-(U1-PA18(SER1:2+)-Pad27)") (class "Default")
      (node (ref "U1") (pin "27") (pinfunction "PA18(SER1:2+)_27") (pintype "bidirectional"))
    )
    (net (code "113") (name "unconnected-(U1-PA27-Pad39)") (class "Default")
      (node (ref "U1") (pin "39") (pinfunction "PA27_39") (pintype "bidirectional"))
    )
    (net (code "114") (name "unconnected-(U1-PB03(AIN11{slash}SER5:1)-Pad48)") (class "Default")
      (node (ref "U1") (pin "48") (pinfunction "PB03(AIN11/SER5:1)_48") (pintype "bidirectional"))
    )
    (net (code "115") (name "unconnected-(U1-PB08(AIN2{slash}SER4:0{slash}TC4:0)-Pad7)") (class "Default")
      (node (ref "U1") (pin "7") (pinfunction "PB08(AIN2/SER4:0/TC4:0)_7") (pintype "bidirectional"))
    )
    (net (code "116") (name "unconnected-(U1-PB22(SER5:2+)-Pad37)") (class "Default")
      (node (ref "U1") (pin "37") (pinfunction "PB22(SER5:2+)_37") (pintype "bidirectional"))
    )
    (net (code "117") (name "unconnected-(U1-PB23(SER5:3+)-Pad38)") (class "Default")
      (node (ref "U1") (pin "38") (pinfunction "PB23(SER5:3+)_38") (pintype "bidirectional"))
    )
  )
)
